# FINAL_COMMON_BOARD.net
KiCad netlist of a schematic drawn in EAGLE
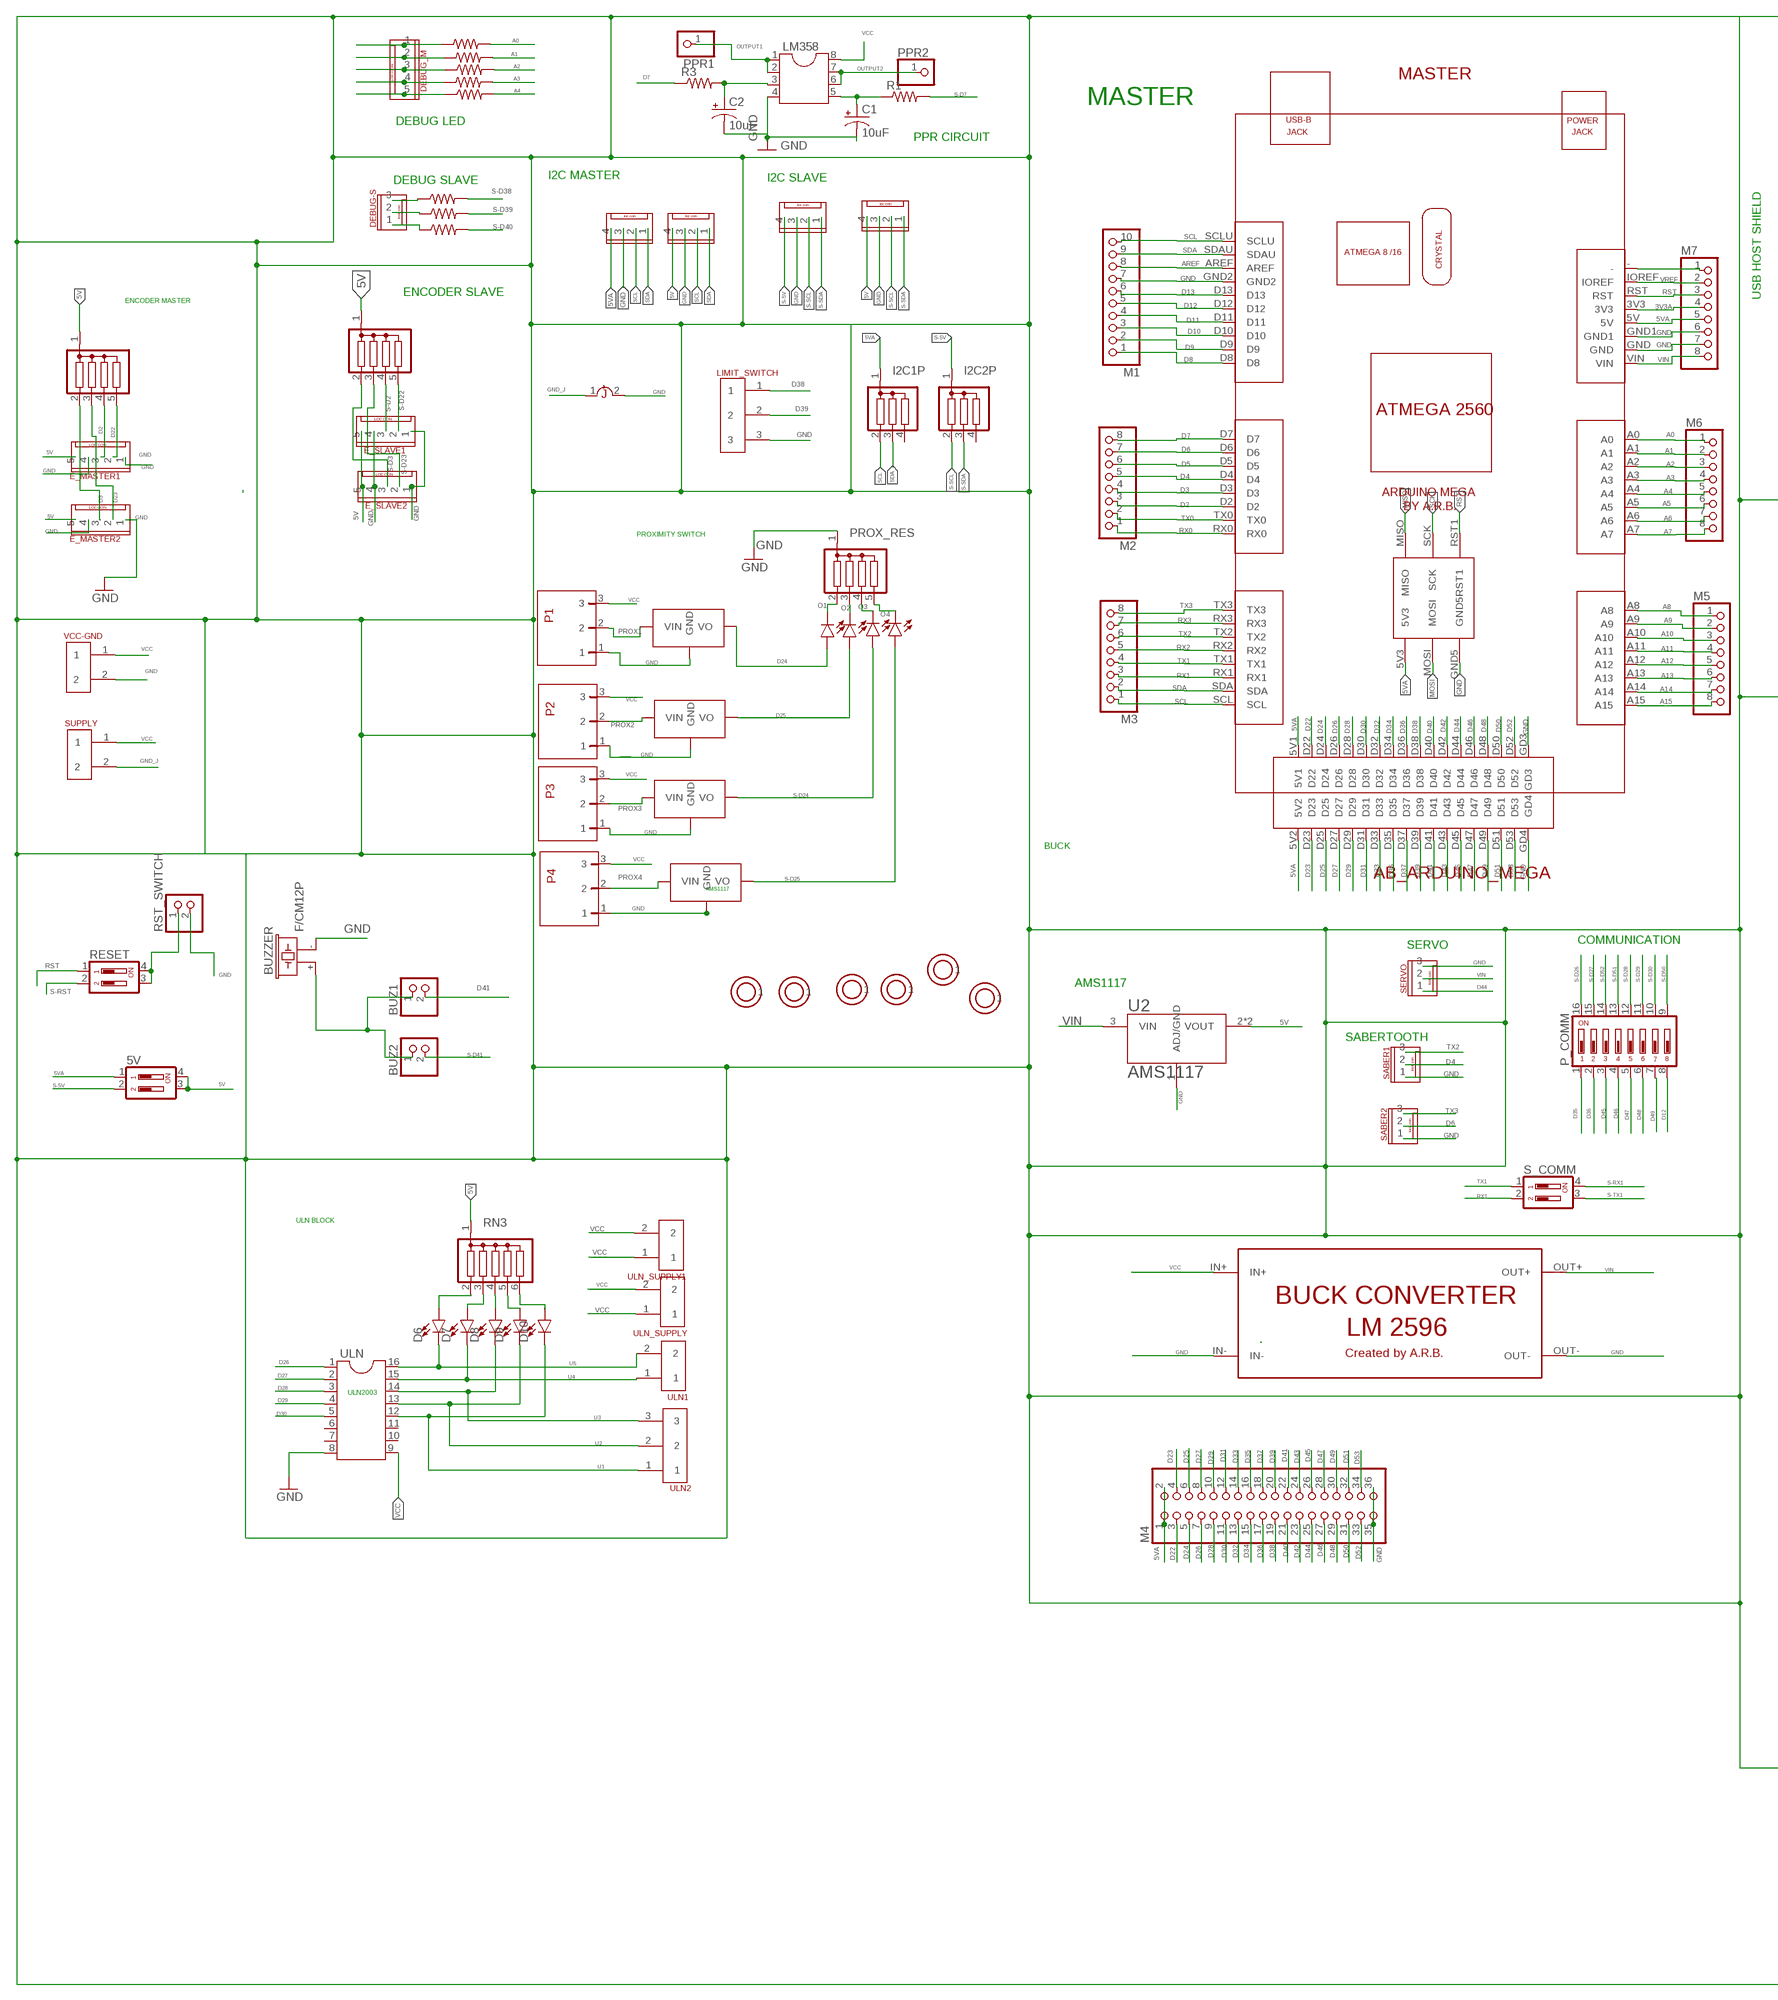
[diagram p0: schematic, sheet 1, part 1 of 2]
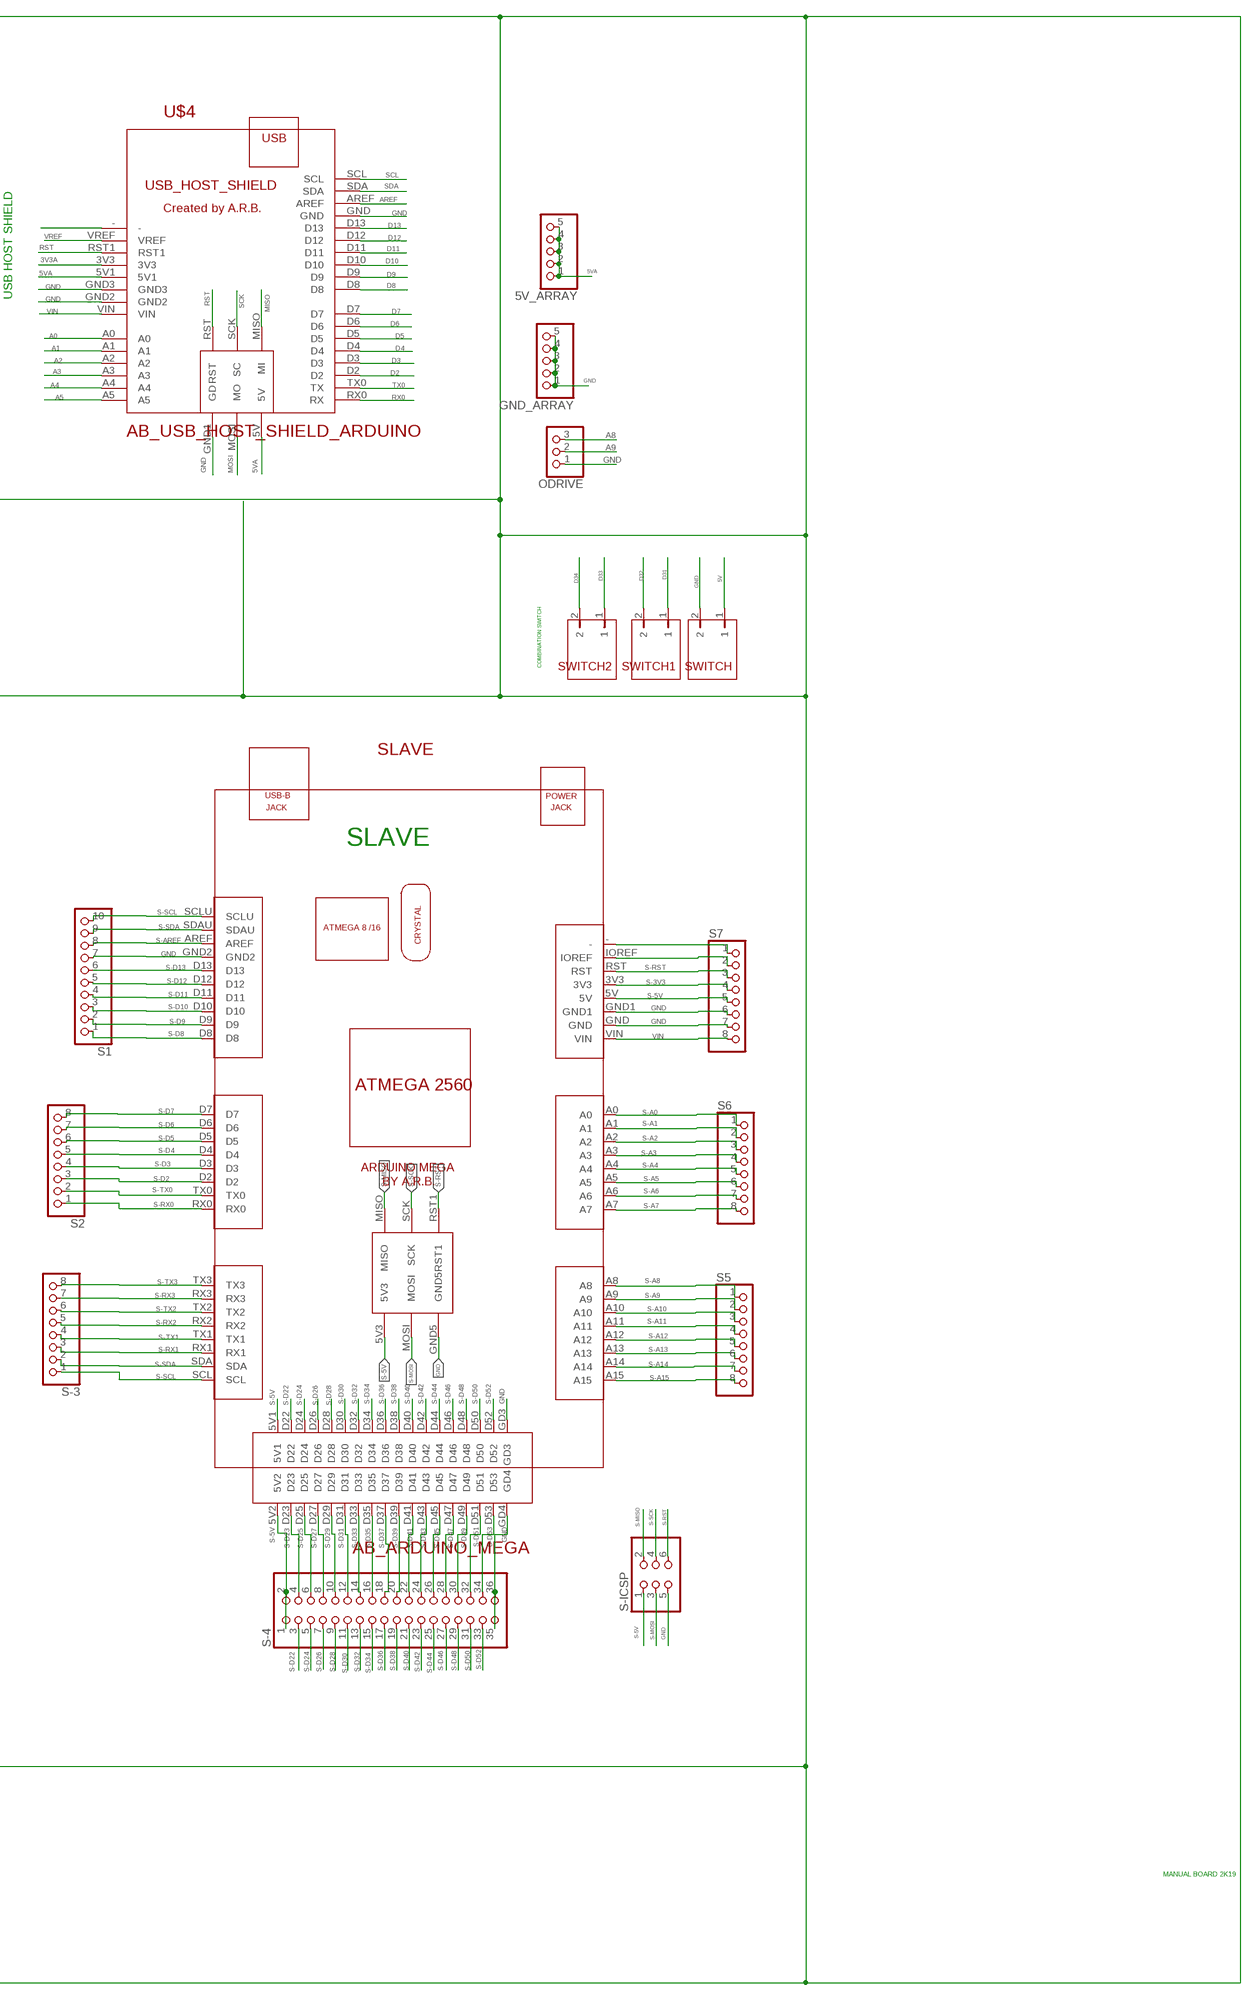
[diagram p1: schematic, sheet 1, part 2 of 2]

(export (version "E")
  (design (tool "Eeschema 10.0.6"))
  (components
    (comp (ref "5V")
      (value "DIP02YL")
      (footprint "eagle-import:DIP02YL")
      (libsource (lib "eagle-import") (part "DIP02YL"))
    )
    (comp (ref "5V_ARRAY")
      (value "PINHD-1X5")
      (footprint "eagle-import:1X05")
      (libsource (lib "eagle-import") (part "PINHD-1X5"))
    )
    (comp (ref "BUZ1")
      (value "PINHD-1X2")
      (footprint "eagle-import:1X02")
      (libsource (lib "eagle-import") (part "PINHD-1X2"))
    )
    (comp (ref "BUZ2")
      (value "PINHD-1X2")
      (footprint "eagle-import:1X02")
      (libsource (lib "eagle-import") (part "PINHD-1X2"))
    )
    (comp (ref "BUZZER")
      (value "F/CM12P")
      (footprint "eagle-import:F_CM12P")
      (libsource (lib "eagle-import") (part "F/CM12P"))
    )
    (comp (ref "C1")
      (value "10uF")
      (footprint "eagle-import:CPOL-RADIAL-2.5MM-5MM")
      (libsource (lib "eagle-import") (part "10UF-POLAR-RADIAL-2.5MM-25V-20%"))
    )
    (comp (ref "C2")
      (value "10uF")
      (footprint "eagle-import:CPOL-RADIAL-2.5MM-5MM")
      (libsource (lib "eagle-import") (part "10UF-POLAR-RADIAL-2.5MM-25V-20%"))
    )
    (comp (ref "D1")
      (value "LED-3MM-NO_SILK")
      (footprint "eagle-import:LED_3MM-NS")
      (libsource (lib "eagle-import") (part "LED-3MM-NO_SILK"))
    )
    (comp (ref "D2")
      (value "LED-3MM-NO_SILK")
      (footprint "eagle-import:LED_3MM-NS")
      (libsource (lib "eagle-import") (part "LED-3MM-NO_SILK"))
    )
    (comp (ref "D3")
      (value "LED-3MM-NO_SILK")
      (footprint "eagle-import:LED_3MM-NS")
      (libsource (lib "eagle-import") (part "LED-3MM-NO_SILK"))
    )
    (comp (ref "D6")
      (value "LED-3MM-NO_SILK")
      (footprint "eagle-import:LED_3MM-NS")
      (libsource (lib "eagle-import") (part "LED-3MM-NO_SILK"))
    )
    (comp (ref "D7")
      (value "LED-3MM-NO_SILK")
      (footprint "eagle-import:LED_3MM-NS")
      (libsource (lib "eagle-import") (part "LED-3MM-NO_SILK"))
    )
    (comp (ref "D8")
      (value "LED-3MM-NO_SILK")
      (footprint "eagle-import:LED_3MM-NS")
      (libsource (lib "eagle-import") (part "LED-3MM-NO_SILK"))
    )
    (comp (ref "D9")
      (value "LED-3MM-NO_SILK")
      (footprint "eagle-import:LED_3MM-NS")
      (libsource (lib "eagle-import") (part "LED-3MM-NO_SILK"))
    )
    (comp (ref "D10")
      (value "LED-3MM-NO_SILK")
      (footprint "eagle-import:LED_3MM-NS")
      (libsource (lib "eagle-import") (part "LED-3MM-NO_SILK"))
    )
    (comp (ref "D14")
      (value "LED-3MM-NO_SILK")
      (footprint "eagle-import:LED_3MM-NS")
      (libsource (lib "eagle-import") (part "LED-3MM-NO_SILK"))
    )
    (comp (ref "DEBUG-S")
      (value "AB_3PIN_LOC_CONNECTOR")
      (footprint "eagle-import:AB_3PIN_LOC_CONNECTOR")
      (libsource (lib "eagle-import") (part "AB_3PIN_LOC_CONNECTOR"))
    )
    (comp (ref "DEBUG_M")
      (value "AB_5PIN_LOC_CONNECTOR")
      (footprint "eagle-import:AB_5PIN_LOC_CONNECTOR")
      (libsource (lib "eagle-import") (part "AB_5PIN_LOC_CONNECTOR"))
    )
    (comp (ref "E_MASTER1")
      (value "AB_5PIN_LOC_CONNECTOR")
      (footprint "eagle-import:AB_5PIN_LOC_CONNECTOR")
      (libsource (lib "eagle-import") (part "AB_5PIN_LOC_CONNECTOR"))
    )
    (comp (ref "E_MASTER2")
      (value "AB_5PIN_LOC_CONNECTOR")
      (footprint "eagle-import:AB_5PIN_LOC_CONNECTOR")
      (libsource (lib "eagle-import") (part "AB_5PIN_LOC_CONNECTOR"))
    )
    (comp (ref "E_SLAVE1")
      (value "AB_5PIN_LOC_CONNECTOR")
      (footprint "eagle-import:AB_5PIN_LOC_CONNECTOR")
      (libsource (lib "eagle-import") (part "AB_5PIN_LOC_CONNECTOR"))
    )
    (comp (ref "E_SLAVE2")
      (value "AB_5PIN_LOC_CONNECTOR")
      (footprint "eagle-import:AB_5PIN_LOC_CONNECTOR")
      (libsource (lib "eagle-import") (part "AB_5PIN_LOC_CONNECTOR"))
    )
    (comp (ref "GND_ARRAY")
      (value "PINHD-1X5")
      (footprint "eagle-import:1X05")
      (libsource (lib "eagle-import") (part "PINHD-1X5"))
    )
    (comp (ref "I2C1P")
      (value "G03R")
      (footprint "eagle-import:SIL4")
      (libsource (lib "eagle-import") (part "G03R"))
    )
    (comp (ref "I2C2P")
      (value "G03R")
      (footprint "eagle-import:SIL4")
      (libsource (lib "eagle-import") (part "G03R"))
    )
    (comp (ref "IMU_BLOCK2")
      (value "AB_4PIN_LOC_CONNECTOR")
      (footprint "eagle-import:AB_4PIN_LOC_CONNECTOR")
      (libsource (lib "eagle-import") (part "AB_4PIN_LOC_CONNECTOR"))
    )
    (comp (ref "IMU_BLOCK3")
      (value "AB_4PIN_LOC_CONNECTOR")
      (footprint "eagle-import:AB_4PIN_LOC_CONNECTOR")
      (libsource (lib "eagle-import") (part "AB_4PIN_LOC_CONNECTOR"))
    )
    (comp (ref "IMU_BLOCK4")
      (value "AB_4PIN_LOC_CONNECTOR")
      (footprint "eagle-import:AB_4PIN_LOC_CONNECTOR")
      (libsource (lib "eagle-import") (part "AB_4PIN_LOC_CONNECTOR"))
    )
    (comp (ref "IMU_MASTER")
      (value "AB_4PIN_LOC_CONNECTOR")
      (footprint "eagle-import:AB_4PIN_LOC_CONNECTOR")
      (libsource (lib "eagle-import") (part "AB_4PIN_LOC_CONNECTOR"))
    )
    (comp (ref "LIMIT_SWITCH")
      (value "AB_SCREW_TER_5MM_3PIN")
      (footprint "eagle-import:AB_SCREW_TER_5MM_3PIN")
      (libsource (lib "eagle-import") (part "AB_SCREW_TER_5MM_3PIN"))
    )
    (comp (ref "LM358")
      (value "DIL8")
      (footprint "eagle-import:DIL08")
      (libsource (lib "eagle-import") (part "DIL8"))
    )
    (comp (ref "M1")
      (value "PINHD-1X10")
      (footprint "eagle-import:1X10")
      (libsource (lib "eagle-import") (part "PINHD-1X10"))
    )
    (comp (ref "M2")
      (value "PINHD-1X8")
      (footprint "eagle-import:1X08")
      (libsource (lib "eagle-import") (part "PINHD-1X8"))
    )
    (comp (ref "M3")
      (value "PINHD-1X8")
      (footprint "eagle-import:1X08")
      (libsource (lib "eagle-import") (part "PINHD-1X8"))
    )
    (comp (ref "M4")
      (value "PINHD-2X18")
      (footprint "eagle-import:2X18")
      (libsource (lib "eagle-import") (part "PINHD-2X18"))
    )
    (comp (ref "M5")
      (value "PINHD-1X8")
      (footprint "eagle-import:1X08")
      (libsource (lib "eagle-import") (part "PINHD-1X8"))
    )
    (comp (ref "M6")
      (value "PINHD-1X8")
      (footprint "eagle-import:1X08")
      (libsource (lib "eagle-import") (part "PINHD-1X8"))
    )
    (comp (ref "M7")
      (value "PINHD-1X8")
      (footprint "eagle-import:1X08")
      (libsource (lib "eagle-import") (part "PINHD-1X8"))
    )
    (comp (ref "MASTER")
      (value "AB_ARDUINO_MEGA")
      (footprint "eagle-import:AB_ARDUINO_MEGA")
      (libsource (lib "eagle-import") (part "AB_ARDUINO_MEGA"))
    )
    (comp (ref "ODRIVE")
      (value "PINHD-1X3")
      (footprint "eagle-import:1X03")
      (libsource (lib "eagle-import") (part "PINHD-1X3"))
    )
    (comp (ref "P1")
      (value "P1")
      (footprint "eagle-import:AB_RIGHT_TER_BLK_3PIN")
      (libsource (lib "eagle-import") (part "AB_RIGHT_TER_BLK_3PIN"))
    )
    (comp (ref "P2")
      (value "P2")
      (footprint "eagle-import:AB_RIGHT_TER_BLK_3PIN")
      (libsource (lib "eagle-import") (part "AB_RIGHT_TER_BLK_3PIN"))
    )
    (comp (ref "P3")
      (value "P3")
      (footprint "eagle-import:AB_RIGHT_TER_BLK_3PIN")
      (libsource (lib "eagle-import") (part "AB_RIGHT_TER_BLK_3PIN"))
    )
    (comp (ref "P4")
      (value "P4")
      (footprint "eagle-import:AB_RIGHT_TER_BLK_3PIN")
      (libsource (lib "eagle-import") (part "AB_RIGHT_TER_BLK_3PIN"))
    )
    (comp (ref "PPR1")
      (value "PINHD-1X1")
      (footprint "eagle-import:1X01")
      (libsource (lib "eagle-import") (part "PINHD-1X1"))
    )
    (comp (ref "PPR2")
      (value "PINHD-1X1")
      (footprint "eagle-import:1X01")
      (libsource (lib "eagle-import") (part "PINHD-1X1"))
    )
    (comp (ref "PROX_RES")
      (value "G04R")
      (footprint "eagle-import:SIL5")
      (libsource (lib "eagle-import") (part "G04R"))
    )
    (comp (ref "PULL_MASTER")
      (value "G04R")
      (footprint "eagle-import:SIL5")
      (libsource (lib "eagle-import") (part "G04R"))
    )
    (comp (ref "PULL_SLAVE")
      (value "G04R")
      (footprint "eagle-import:SIL5")
      (libsource (lib "eagle-import") (part "G04R"))
    )
    (comp (ref "P_COMM")
      (value "DIP08YL")
      (footprint "eagle-import:DIP08YL")
      (libsource (lib "eagle-import") (part "DIP08YL"))
    )
    (comp (ref "R1")
      (value "R-US_0204/7")
      (footprint "eagle-import:0204_7")
      (libsource (lib "eagle-import") (part "R-US_0204/7"))
    )
    (comp (ref "R2")
      (value "R-US_0204/7")
      (footprint "eagle-import:0204_7")
      (libsource (lib "eagle-import") (part "R-US_0204/7"))
    )
    (comp (ref "R3")
      (value "R-US_0204/7")
      (footprint "eagle-import:0204_7")
      (libsource (lib "eagle-import") (part "R-US_0204/7"))
    )
    (comp (ref "R4")
      (value "R-US_0204/7")
      (footprint "eagle-import:0204_7")
      (libsource (lib "eagle-import") (part "R-US_0204/7"))
    )
    (comp (ref "R5")
      (value "R-US_0204/7")
      (footprint "eagle-import:0204_7")
      (libsource (lib "eagle-import") (part "R-US_0204/7"))
    )
    (comp (ref "R6")
      (value "R-US_0204/7")
      (footprint "eagle-import:0204_7")
      (libsource (lib "eagle-import") (part "R-US_0204/7"))
    )
    (comp (ref "R7")
      (value "R-US_0204/7")
      (footprint "eagle-import:0204_7")
      (libsource (lib "eagle-import") (part "R-US_0204/7"))
    )
    (comp (ref "R8")
      (value "R-US_0204/7")
      (footprint "eagle-import:0204_7")
      (libsource (lib "eagle-import") (part "R-US_0204/7"))
    )
    (comp (ref "R9")
      (value "R-US_0204/7")
      (footprint "eagle-import:0204_7")
      (libsource (lib "eagle-import") (part "R-US_0204/7"))
    )
    (comp (ref "R10")
      (value "R-US_0204/7")
      (footprint "eagle-import:0204_7")
      (libsource (lib "eagle-import") (part "R-US_0204/7"))
    )
    (comp (ref "RESET")
      (value "DIP02YL")
      (footprint "eagle-import:DIP02YL")
      (libsource (lib "eagle-import") (part "DIP02YL"))
    )
    (comp (ref "RN3")
      (value "G05R")
      (footprint "eagle-import:SIL6")
      (libsource (lib "eagle-import") (part "G05R"))
    )
    (comp (ref "RST_SWITCH")
      (value "PINHD-1X2")
      (footprint "eagle-import:1X02")
      (libsource (lib "eagle-import") (part "PINHD-1X2"))
    )
    (comp (ref "S-3")
      (value "PINHD-1X8")
      (footprint "eagle-import:1X08")
      (libsource (lib "eagle-import") (part "PINHD-1X8"))
    )
    (comp (ref "S-4")
      (value "PINHD-2X18")
      (footprint "eagle-import:2X18")
      (libsource (lib "eagle-import") (part "PINHD-2X18"))
    )
    (comp (ref "S-ICSP")
      (value "PINHD-2X3")
      (footprint "eagle-import:2X03")
      (libsource (lib "eagle-import") (part "PINHD-2X3"))
    )
    (comp (ref "S1")
      (value "PINHD-1X10")
      (footprint "eagle-import:1X10")
      (libsource (lib "eagle-import") (part "PINHD-1X10"))
    )
    (comp (ref "S2")
      (value "PINHD-1X8")
      (footprint "eagle-import:1X08")
      (libsource (lib "eagle-import") (part "PINHD-1X8"))
    )
    (comp (ref "S5")
      (value "PINHD-1X8")
      (footprint "eagle-import:1X08")
      (libsource (lib "eagle-import") (part "PINHD-1X8"))
    )
    (comp (ref "S6")
      (value "PINHD-1X8")
      (footprint "eagle-import:1X08")
      (libsource (lib "eagle-import") (part "PINHD-1X8"))
    )
    (comp (ref "S7")
      (value "PINHD-1X8")
      (footprint "eagle-import:1X08")
      (libsource (lib "eagle-import") (part "PINHD-1X8"))
    )
    (comp (ref "SABER1")
      (value "AB_3PIN_LOC_CONNECTOR")
      (footprint "eagle-import:AB_3PIN_LOC_CONNECTOR")
      (libsource (lib "eagle-import") (part "AB_3PIN_LOC_CONNECTOR"))
    )
    (comp (ref "SABER2")
      (value "AB_3PIN_LOC_CONNECTOR")
      (footprint "eagle-import:AB_3PIN_LOC_CONNECTOR")
      (libsource (lib "eagle-import") (part "AB_3PIN_LOC_CONNECTOR"))
    )
    (comp (ref "SERVO")
      (value "AB_3PIN_LOC_CONNECTOR")
      (footprint "eagle-import:AB_3PIN_LOC_CONNECTOR")
      (libsource (lib "eagle-import") (part "AB_3PIN_LOC_CONNECTOR"))
    )
    (comp (ref "SLAVE")
      (value "AB_ARDUINO_MEGA")
      (footprint "eagle-import:AB_ARDUINO_MEGA")
      (libsource (lib "eagle-import") (part "AB_ARDUINO_MEGA"))
    )
    (comp (ref "SUPPLY")
      (value "AB_SCREW_TERMINAL_5MM_2PIN")
      (footprint "eagle-import:AB_SCREW_TERMINAL_5MM_2PIN")
      (libsource (lib "eagle-import") (part "AB_SCREW_TERMINAL_5MM_2PIN"))
    )
    (comp (ref "SWITCH")
      (value "AB_RIGHT_TER_BLK")
      (footprint "eagle-import:AB_RIGHT_TER_BLK")
      (libsource (lib "eagle-import") (part "AB_RIGHT_TER_BLK"))
    )
    (comp (ref "SWITCH1")
      (value "AB_RIGHT_TER_BLK")
      (footprint "eagle-import:AB_RIGHT_TER_BLK")
      (libsource (lib "eagle-import") (part "AB_RIGHT_TER_BLK"))
    )
    (comp (ref "SWITCH2")
      (value "AB_RIGHT_TER_BLK")
      (footprint "eagle-import:AB_RIGHT_TER_BLK")
      (libsource (lib "eagle-import") (part "AB_RIGHT_TER_BLK"))
    )
    (comp (ref "S_COMM")
      (value "DIP02YL")
      (footprint "eagle-import:DIP02YL")
      (libsource (lib "eagle-import") (part "DIP02YL"))
    )
    (comp (ref "U$1")
      (value "PLATED_DRILL_3.5MM")
      (footprint "eagle-import:PLATED_DRILL_3.5MM")
      (libsource (lib "eagle-import") (part "PLATED_DRILL_3.5MM"))
    )
    (comp (ref "U$2")
      (value "PLATED_DRILL_3.5MM")
      (footprint "eagle-import:PLATED_DRILL_3.5MM")
      (libsource (lib "eagle-import") (part "PLATED_DRILL_3.5MM"))
    )
    (comp (ref "U$3")
      (value "AB_LM2596_BUCK_CONVERTER")
      (footprint "eagle-import:AB_LM2596_BUCK_CONVERTER")
      (libsource (lib "eagle-import") (part "AB_LM2596_BUCK_CONVERTER"))
    )
    (comp (ref "U$4")
      (value "AB_USB_HOST_SHIELD_ARDUINO")
      (footprint "eagle-import:AB_USB_HOST_SHIELD_ARDUINO")
      (libsource (lib "eagle-import") (part "AB_USB_HOST_SHIELD_ARDUINO"))
    )
    (comp (ref "U$5")
      (value "PLATED_DRILL_3.5MM")
      (footprint "eagle-import:PLATED_DRILL_3.5MM")
      (libsource (lib "eagle-import") (part "PLATED_DRILL_3.5MM"))
    )
    (comp (ref "U$6")
      (value "PLATED_DRILL_3.5MM")
      (footprint "eagle-import:PLATED_DRILL_3.5MM")
      (libsource (lib "eagle-import") (part "PLATED_DRILL_3.5MM"))
    )
    (comp (ref "U$7")
      (value "PLATED_DRILL_3.5MM")
      (footprint "eagle-import:PLATED_DRILL_3.5MM")
      (libsource (lib "eagle-import") (part "PLATED_DRILL_3.5MM"))
    )
    (comp (ref "U$8")
      (value "PLATED_DRILL_3.5MM")
      (footprint "eagle-import:PLATED_DRILL_3.5MM")
      (libsource (lib "eagle-import") (part "PLATED_DRILL_3.5MM"))
    )
    (comp (ref "U$23")
      (value "AB_7805_FLAT")
      (footprint "eagle-import:AB_7805_FLAT")
      (libsource (lib "eagle-import") (part "AB_7805_FLAT"))
    )
    (comp (ref "U$24")
      (value "AB_7805_FLAT")
      (footprint "eagle-import:AB_7805_FLAT")
      (libsource (lib "eagle-import") (part "AB_7805_FLAT"))
    )
    (comp (ref "U$25")
      (value "AB_7805_FLAT")
      (footprint "eagle-import:AB_7805_FLAT")
      (libsource (lib "eagle-import") (part "AB_7805_FLAT"))
    )
    (comp (ref "U$26")
      (value "AB_7805_FLAT")
      (footprint "eagle-import:AB_7805_FLAT")
      (libsource (lib "eagle-import") (part "AB_7805_FLAT"))
    )
    (comp (ref "U$35")
      (value "AB_JUMPER_ONE_WAY")
      (footprint "eagle-import:AB_JUMPER_ONE_WAY")
      (libsource (lib "eagle-import") (part "AB_JUMPER_ONE_WAY"))
    )
    (comp (ref "U2")
      (value "AMS1117")
      (footprint "eagle-import:SOT229P700X180-4N")
      (fields (field (name "MF") "Seeed Technology"))
      (libsource (lib "eagle-import") (part "AMS1117"))
    )
    (comp (ref "ULN")
      (value "DIL16")
      (footprint "eagle-import:DIL16")
      (libsource (lib "eagle-import") (part "DIL16"))
    )
    (comp (ref "ULN1")
      (value "AB_SCREW_TERMINAL_5MM_2PIN")
      (footprint "eagle-import:AB_SCREW_TERMINAL_5MM_2PIN")
      (libsource (lib "eagle-import") (part "AB_SCREW_TERMINAL_5MM_2PIN"))
    )
    (comp (ref "ULN2")
      (value "AB_SCREW_TER_5MM_3PIN")
      (footprint "eagle-import:AB_SCREW_TER_5MM_3PIN")
      (libsource (lib "eagle-import") (part "AB_SCREW_TER_5MM_3PIN"))
    )
    (comp (ref "ULN_SUPPLY")
      (value "AB_SCREW_TERMINAL_5MM_2PIN")
      (footprint "eagle-import:AB_SCREW_TERMINAL_5MM_2PIN")
      (libsource (lib "eagle-import") (part "AB_SCREW_TERMINAL_5MM_2PIN"))
    )
    (comp (ref "ULN_SUPPLY1")
      (value "AB_SCREW_TERMINAL_5MM_2PIN")
      (footprint "eagle-import:AB_SCREW_TERMINAL_5MM_2PIN")
      (libsource (lib "eagle-import") (part "AB_SCREW_TERMINAL_5MM_2PIN"))
    )
    (comp (ref "VCC-GND")
      (value "AB_SCREW_TERMINAL_5MM_2PIN")
      (footprint "eagle-import:AB_SCREW_TERMINAL_5MM_2PIN")
      (libsource (lib "eagle-import") (part "AB_SCREW_TERMINAL_5MM_2PIN"))
    )
  )
  (nets
    (net (code "1") (name "/3V3A") (class "Default")
      (node (ref "M7") (pin "4") (pinfunction "4_4") (pintype "passive"))
      (node (ref "MASTER") (pin "3V3") (pinfunction "3V3_3V3") (pintype "bidirectional"))
      (node (ref "U$4") (pin "3V3") (pinfunction "3V3_3V3") (pintype "bidirectional"))
    )
    (net (code "2") (name "/A0") (class "Default")
      (node (ref "M6") (pin "1") (pinfunction "1_1") (pintype "passive"))
      (node (ref "MASTER") (pin "A0") (pinfunction "A0_A0") (pintype "bidirectional"))
      (node (ref "R2") (pin "2") (pinfunction "2_2") (pintype "passive"))
      (node (ref "U$4") (pin "A0") (pinfunction "A0_A0") (pintype "bidirectional"))
    )
    (net (code "3") (name "/A1") (class "Default")
      (node (ref "M6") (pin "2") (pinfunction "2_2") (pintype "passive"))
      (node (ref "MASTER") (pin "A1") (pinfunction "A1_A1") (pintype "bidirectional"))
      (node (ref "R4") (pin "2") (pinfunction "2_2") (pintype "passive"))
      (node (ref "U$4") (pin "A1") (pinfunction "A1_A1") (pintype "bidirectional"))
    )
    (net (code "4") (name "/A2") (class "Default")
      (node (ref "M6") (pin "3") (pinfunction "3_3") (pintype "passive"))
      (node (ref "MASTER") (pin "A2") (pinfunction "A2_A2") (pintype "bidirectional"))
      (node (ref "R5") (pin "2") (pinfunction "2_2") (pintype "passive"))
      (node (ref "U$4") (pin "A2") (pinfunction "A2_A2") (pintype "bidirectional"))
    )
    (net (code "5") (name "/A3") (class "Default")
      (node (ref "M6") (pin "4") (pinfunction "4_4") (pintype "passive"))
      (node (ref "MASTER") (pin "A3") (pinfunction "A3_A3") (pintype "bidirectional"))
      (node (ref "R6") (pin "2") (pinfunction "2_2") (pintype "passive"))
      (node (ref "U$4") (pin "A3") (pinfunction "A3_A3") (pintype "bidirectional"))
    )
    (net (code "6") (name "/A4") (class "Default")
      (node (ref "M6") (pin "5") (pinfunction "5_5") (pintype "passive"))
      (node (ref "MASTER") (pin "A4") (pinfunction "A4_A4") (pintype "bidirectional"))
      (node (ref "R7") (pin "2") (pinfunction "2_2") (pintype "passive"))
      (node (ref "U$4") (pin "A4") (pinfunction "A4_A4") (pintype "bidirectional"))
    )
    (net (code "7") (name "/A5") (class "Default")
      (node (ref "M6") (pin "6") (pinfunction "6_6") (pintype "passive"))
      (node (ref "MASTER") (pin "A5") (pinfunction "A5_A5") (pintype "bidirectional"))
      (node (ref "U$4") (pin "A5") (pinfunction "A5_A5") (pintype "bidirectional"))
    )
    (net (code "8") (name "/A6") (class "Default")
      (node (ref "M6") (pin "7") (pinfunction "7_7") (pintype "passive"))
      (node (ref "MASTER") (pin "A6") (pinfunction "A6_A6") (pintype "bidirectional"))
    )
    (net (code "9") (name "/A7") (class "Default")
      (node (ref "M6") (pin "8") (pinfunction "8_8") (pintype "passive"))
      (node (ref "MASTER") (pin "A7") (pinfunction "A7_A7") (pintype "bidirectional"))
    )
    (net (code "10") (name "/A8") (class "Default")
      (node (ref "M5") (pin "1") (pinfunction "1_1") (pintype "passive"))
      (node (ref "MASTER") (pin "A8") (pinfunction "A8_A8") (pintype "bidirectional"))
      (node (ref "ODRIVE") (pin "3") (pinfunction "3_3") (pintype "passive"))
    )
    (net (code "11") (name "/A9") (class "Default")
      (node (ref "M5") (pin "2") (pinfunction "2_2") (pintype "passive"))
      (node (ref "MASTER") (pin "A9") (pinfunction "A9_A9") (pintype "bidirectional"))
      (node (ref "ODRIVE") (pin "2") (pinfunction "2_2") (pintype "passive"))
    )
    (net (code "12") (name "/A10") (class "Default")
      (node (ref "M5") (pin "3") (pinfunction "3_3") (pintype "passive"))
      (node (ref "MASTER") (pin "A10") (pinfunction "A10_A10") (pintype "bidirectional"))
    )
    (net (code "13") (name "/A11") (class "Default")
      (node (ref "M5") (pin "4") (pinfunction "4_4") (pintype "passive"))
      (node (ref "MASTER") (pin "A11") (pinfunction "A11_A11") (pintype "bidirectional"))
    )
    (net (code "14") (name "/A12") (class "Default")
      (node (ref "M5") (pin "5") (pinfunction "5_5") (pintype "passive"))
      (node (ref "MASTER") (pin "A12") (pinfunction "A12_A12") (pintype "bidirectional"))
    )
    (net (code "15") (name "/A13") (class "Default")
      (node (ref "M5") (pin "6") (pinfunction "6_6") (pintype "passive"))
      (node (ref "MASTER") (pin "A13") (pinfunction "A13_A13") (pintype "bidirectional"))
    )
    (net (code "16") (name "/A14") (class "Default")
      (node (ref "M5") (pin "7") (pinfunction "7_7") (pintype "passive"))
      (node (ref "MASTER") (pin "A14") (pinfunction "A14_A14") (pintype "bidirectional"))
    )
    (net (code "17") (name "/A15") (class "Default")
      (node (ref "M5") (pin "8") (pinfunction "8_8") (pintype "passive"))
      (node (ref "MASTER") (pin "A15") (pinfunction "A15_A15") (pintype "bidirectional"))
    )
    (net (code "18") (name "/AREF") (class "Default")
      (node (ref "M1") (pin "8") (pinfunction "8_8") (pintype "passive"))
      (node (ref "MASTER") (pin "AREF") (pinfunction "AREF_AREF") (pintype "bidirectional"))
      (node (ref "U$4") (pin "AREF") (pinfunction "AREF_AREF") (pintype "bidirectional"))
    )
    (net (code "19") (name "/D2") (class "Default")
      (node (ref "E_MASTER1") (pin "3") (pinfunction "3_3") (pintype "bidirectional"))
      (node (ref "M2") (pin "3") (pinfunction "3_3") (pintype "passive"))
      (node (ref "MASTER") (pin "D2") (pinfunction "D2_D2") (pintype "bidirectional"))
      (node (ref "PULL_MASTER") (pin "4") (pinfunction "4_4") (pintype "passive"))
      (node (ref "U$4") (pin "D2") (pinfunction "D2_D2") (pintype "bidirectional"))
    )
    (net (code "20") (name "/D3") (class "Default")
      (node (ref "E_MASTER2") (pin "3") (pinfunction "3_3") (pintype "bidirectional"))
      (node (ref "M2") (pin "4") (pinfunction "4_4") (pintype "passive"))
      (node (ref "MASTER") (pin "D3") (pinfunction "D3_D3") (pintype "bidirectional"))
      (node (ref "PULL_MASTER") (pin "2") (pinfunction "2_2") (pintype "passive"))
      (node (ref "U$4") (pin "D3") (pinfunction "D3_D3") (pintype "bidirectional"))
    )
    (net (code "21") (name "/D4") (class "Default")
      (node (ref "M2") (pin "5") (pinfunction "5_5") (pintype "passive"))
      (node (ref "MASTER") (pin "D4") (pinfunction "D4_D4") (pintype "bidirectional"))
      (node (ref "SABER1") (pin "2") (pinfunction "2_2") (pintype "bidirectional"))
      (node (ref "U$4") (pin "D4") (pinfunction "D4_D4") (pintype "bidirectional"))
    )
    (net (code "22") (name "/D5") (class "Default")
      (node (ref "M2") (pin "6") (pinfunction "6_6") (pintype "passive"))
      (node (ref "MASTER") (pin "D5") (pinfunction "D5_D5") (pintype "bidirectional"))
      (node (ref "U$4") (pin "D5") (pinfunction "D5_D5") (pintype "bidirectional"))
    )
    (net (code "23") (name "/D6") (class "Default")
      (node (ref "M2") (pin "7") (pinfunction "7_7") (pintype "passive"))
      (node (ref "MASTER") (pin "D6") (pinfunction "D6_D6") (pintype "bidirectional"))
      (node (ref "SABER2") (pin "2") (pinfunction "2_2") (pintype "bidirectional"))
      (node (ref "U$4") (pin "D6") (pinfunction "D6_D6") (pintype "bidirectional"))
    )
    (net (code "24") (name "/D7") (class "Default")
      (node (ref "M2") (pin "8") (pinfunction "8_8") (pintype "passive"))
      (node (ref "MASTER") (pin "D7") (pinfunction "D7_D7") (pintype "bidirectional"))
      (node (ref "R3") (pin "1") (pinfunction "1_1") (pintype "passive"))
      (node (ref "U$4") (pin "D7") (pinfunction "D7_D7") (pintype "bidirectional"))
    )
    (net (code "25") (name "/D8") (class "Default")
      (node (ref "M1") (pin "1") (pinfunction "1_1") (pintype "passive"))
      (node (ref "MASTER") (pin "D8") (pinfunction "D8_D8") (pintype "bidirectional"))
      (node (ref "U$4") (pin "D8") (pinfunction "D8_D8") (pintype "bidirectional"))
    )
    (net (code "26") (name "/D9") (class "Default")
      (node (ref "M1") (pin "2") (pinfunction "2_2") (pintype "passive"))
      (node (ref "MASTER") (pin "D9") (pinfunction "D9_D9") (pintype "bidirectional"))
      (node (ref "U$4") (pin "D9") (pinfunction "D9_D9") (pintype "bidirectional"))
    )
    (net (code "27") (name "/D10") (class "Default")
      (node (ref "M1") (pin "3") (pinfunction "3_3") (pintype "passive"))
      (node (ref "MASTER") (pin "D10") (pinfunction "D10_D10") (pintype "bidirectional"))
      (node (ref "U$4") (pin "D10") (pinfunction "D10_D10") (pintype "bidirectional"))
    )
    (net (code "28") (name "/D11") (class "Default")
      (node (ref "M1") (pin "4") (pinfunction "4_4") (pintype "passive"))
      (node (ref "MASTER") (pin "D11") (pinfunction "D11_D11") (pintype "bidirectional"))
      (node (ref "U$4") (pin "D11") (pinfunction "D11_D11") (pintype "bidirectional"))
    )
    (net (code "29") (name "/D12") (class "Default")
      (node (ref "M1") (pin "5") (pinfunction "5_5") (pintype "passive"))
      (node (ref "MASTER") (pin "D12") (pinfunction "D12_D12") (pintype "bidirectional"))
      (node (ref "P_COMM") (pin "8") (pinfunction "8_8") (pintype "passive"))
      (node (ref "U$4") (pin "D12") (pinfunction "D12_D12") (pintype "bidirectional"))
    )
    (net (code "30") (name "/D13") (class "Default")
      (node (ref "M1") (pin "6") (pinfunction "6_6") (pintype "passive"))
      (node (ref "MASTER") (pin "D13") (pinfunction "D13_D13") (pintype "bidirectional"))
      (node (ref "U$4") (pin "D13") (pinfunction "D13_D13") (pintype "bidirectional"))
    )
    (net (code "31") (name "/D22") (class "Default")
      (node (ref "E_MASTER1") (pin "2") (pinfunction "2_2") (pintype "bidirectional"))
      (node (ref "M4") (pin "3") (pinfunction "3_3") (pintype "passive"))
      (node (ref "MASTER") (pin "D22") (pinfunction "D22_D22") (pintype "bidirectional"))
      (node (ref "PULL_MASTER") (pin "5") (pinfunction "5_5") (pintype "passive"))
    )
    (net (code "32") (name "/D23") (class "Default")
      (node (ref "E_MASTER2") (pin "2") (pinfunction "2_2") (pintype "bidirectional"))
      (node (ref "M4") (pin "4") (pinfunction "4_4") (pintype "passive"))
      (node (ref "MASTER") (pin "D23") (pinfunction "D23_D23") (pintype "bidirectional"))
      (node (ref "PULL_MASTER") (pin "3") (pinfunction "3_3") (pintype "passive"))
    )
    (net (code "33") (name "/D24") (class "Default")
      (node (ref "D14") (pin "A") (pinfunction "A_A") (pintype "passive"))
      (node (ref "M4") (pin "5") (pinfunction "5_5") (pintype "passive"))
      (node (ref "MASTER") (pin "D24") (pinfunction "D24_D24") (pintype "bidirectional"))
      (node (ref "U$23") (pin "3") (pinfunction "VO_3") (pintype "bidirectional"))
    )
    (net (code "34") (name "/D25") (class "Default")
      (node (ref "D1") (pin "A") (pinfunction "A_A") (pintype "passive"))
      (node (ref "M4") (pin "6") (pinfunction "6_6") (pintype "passive"))
      (node (ref "MASTER") (pin "D25") (pinfunction "D25_D25") (pintype "bidirectional"))
      (node (ref "U$24") (pin "3") (pinfunction "VO_3") (pintype "bidirectional"))
    )
    (net (code "35") (name "/D26") (class "Default")
      (node (ref "M4") (pin "7") (pinfunction "7_7") (pintype "passive"))
      (node (ref "MASTER") (pin "D26") (pinfunction "D26_D26") (pintype "bidirectional"))
      (node (ref "ULN") (pin "1") (pinfunction "1_1") (pintype "passive"))
    )
    (net (code "36") (name "/D27") (class "Default")
      (node (ref "M4") (pin "8") (pinfunction "8_8") (pintype "passive"))
      (node (ref "MASTER") (pin "D27") (pinfunction "D27_D27") (pintype "bidirectional"))
      (node (ref "ULN") (pin "2") (pinfunction "2_2") (pintype "passive"))
    )
    (net (code "37") (name "/D28") (class "Default")
      (node (ref "M4") (pin "9") (pinfunction "9_9") (pintype "passive"))
      (node (ref "MASTER") (pin "D28") (pinfunction "D28_D28") (pintype "bidirectional"))
      (node (ref "ULN") (pin "3") (pinfunction "3_3") (pintype "passive"))
    )
    (net (code "38") (name "/D29") (class "Default")
      (node (ref "M4") (pin "10") (pinfunction "10_10") (pintype "passive"))
      (node (ref "MASTER") (pin "D29") (pinfunction "D29_D29") (pintype "bidirectional"))
      (node (ref "ULN") (pin "4") (pinfunction "4_4") (pintype "passive"))
    )
    (net (code "39") (name "/D30") (class "Default")
      (node (ref "M4") (pin "11") (pinfunction "11_11") (pintype "passive"))
      (node (ref "MASTER") (pin "D30") (pinfunction "D30_D30") (pintype "bidirectional"))
      (node (ref "ULN") (pin "5") (pinfunction "5_5") (pintype "passive"))
    )
    (net (code "40") (name "/D31") (class "Default")
      (node (ref "M4") (pin "12") (pinfunction "12_12") (pintype "passive"))
      (node (ref "MASTER") (pin "D31") (pinfunction "D31_D31") (pintype "bidirectional"))
      (node (ref "SWITCH1") (pin "1") (pinfunction "1_1") (pintype "bidirectional"))
    )
    (net (code "41") (name "/D32") (class "Default")
      (node (ref "M4") (pin "13") (pinfunction "13_13") (pintype "passive"))
      (node (ref "MASTER") (pin "D32") (pinfunction "D32_D32") (pintype "bidirectional"))
      (node (ref "SWITCH1") (pin "2") (pinfunction "2_2") (pintype "bidirectional"))
    )
    (net (code "42") (name "/D33") (class "Default")
      (node (ref "M4") (pin "14") (pinfunction "14_14") (pintype "passive"))
      (node (ref "MASTER") (pin "D33") (pinfunction "D33_D33") (pintype "bidirectional"))
      (node (ref "SWITCH2") (pin "1") (pinfunction "1_1") (pintype "bidirectional"))
    )
    (net (code "43") (name "/D34") (class "Default")
      (node (ref "M4") (pin "15") (pinfunction "15_15") (pintype "passive"))
      (node (ref "MASTER") (pin "D34") (pinfunction "D34_D34") (pintype "bidirectional"))
      (node (ref "SWITCH2") (pin "2") (pinfunction "2_2") (pintype "bidirectional"))
    )
    (net (code "44") (name "/D35") (class "Default")
      (node (ref "M4") (pin "16") (pinfunction "16_16") (pintype "passive"))
      (node (ref "MASTER") (pin "D35") (pinfunction "D35_D35") (pintype "bidirectional"))
      (node (ref "P_COMM") (pin "1") (pinfunction "1_1") (pintype "passive"))
    )
    (net (code "45") (name "/D36") (class "Default")
      (node (ref "M4") (pin "17") (pinfunction "17_17") (pintype "passive"))
      (node (ref "MASTER") (pin "D36") (pinfunction "D36_D36") (pintype "bidirectional"))
      (node (ref "P_COMM") (pin "2") (pinfunction "2_2") (pintype "passive"))
    )
    (net (code "46") (name "/D37") (class "Default")
      (node (ref "M4") (pin "18") (pinfunction "18_18") (pintype "passive"))
      (node (ref "MASTER") (pin "D37") (pinfunction "D37_D37") (pintype "bidirectional"))
    )
    (net (code "47") (name "/D38") (class "Default")
      (node (ref "LIMIT_SWITCH") (pin "1") (pinfunction "1_1") (pintype "bidirectional"))
      (node (ref "M4") (pin "19") (pinfunction "19_19") (pintype "passive"))
      (node (ref "MASTER") (pin "D38") (pinfunction "D38_D38") (pintype "bidirectional"))
    )
    (net (code "48") (name "/D39") (class "Default")
      (node (ref "LIMIT_SWITCH") (pin "2") (pinfunction "2_2") (pintype "bidirectional"))
      (node (ref "M4") (pin "20") (pinfunction "20_20") (pintype "passive"))
      (node (ref "MASTER") (pin "D39") (pinfunction "D39_D39") (pintype "bidirectional"))
    )
    (net (code "49") (name "/D40") (class "Default")
      (node (ref "M4") (pin "21") (pinfunction "21_21") (pintype "passive"))
      (node (ref "MASTER") (pin "D40") (pinfunction "D40_D40") (pintype "bidirectional"))
    )
    (net (code "50") (name "/D41") (class "Default")
      (node (ref "BUZ1") (pin "2") (pinfunction "2_2") (pintype "passive"))
      (node (ref "M4") (pin "22") (pinfunction "22_22") (pintype "passive"))
      (node (ref "MASTER") (pin "D41") (pinfunction "D41_D41") (pintype "bidirectional"))
    )
    (net (code "51") (name "/D42") (class "Default")
      (node (ref "M4") (pin "23") (pinfunction "23_23") (pintype "passive"))
      (node (ref "MASTER") (pin "D42") (pinfunction "D42_D42") (pintype "bidirectional"))
    )
    (net (code "52") (name "/D43") (class "Default")
      (node (ref "M4") (pin "24") (pinfunction "24_24") (pintype "passive"))
      (node (ref "MASTER") (pin "D43") (pinfunction "D43_D43") (pintype "bidirectional"))
    )
    (net (code "53") (name "/D44") (class "Default")
      (node (ref "M4") (pin "25") (pinfunction "25_25") (pintype "passive"))
      (node (ref "MASTER") (pin "D44") (pinfunction "D44_D44") (pintype "bidirectional"))
      (node (ref "SERVO") (pin "1") (pinfunction "1_1") (pintype "bidirectional"))
    )
    (net (code "54") (name "/D45") (class "Default")
      (node (ref "M4") (pin "26") (pinfunction "26_26") (pintype "passive"))
      (node (ref "MASTER") (pin "D45") (pinfunction "D45_D45") (pintype "bidirectional"))
      (node (ref "P_COMM") (pin "3") (pinfunction "3_3") (pintype "passive"))
    )
    (net (code "55") (name "/D46") (class "Default")
      (node (ref "M4") (pin "27") (pinfunction "27_27") (pintype "passive"))
      (node (ref "MASTER") (pin "D46") (pinfunction "D46_D46") (pintype "bidirectional"))
      (node (ref "P_COMM") (pin "4") (pinfunction "4_4") (pintype "passive"))
    )
    (net (code "56") (name "/D47") (class "Default")
      (node (ref "M4") (pin "28") (pinfunction "28_28") (pintype "passive"))
      (node (ref "MASTER") (pin "D47") (pinfunction "D47_D47") (pintype "bidirectional"))
      (node (ref "P_COMM") (pin "5") (pinfunction "5_5") (pintype "passive"))
    )
    (net (code "57") (name "/D48") (class "Default")
      (node (ref "M4") (pin "29") (pinfunction "29_29") (pintype "passive"))
      (node (ref "MASTER") (pin "D48") (pinfunction "D48_D48") (pintype "bidirectional"))
      (node (ref "P_COMM") (pin "6") (pinfunction "6_6") (pintype "passive"))
    )
    (net (code "58") (name "/D49") (class "Default")
      (node (ref "M4") (pin "30") (pinfunction "30_30") (pintype "passive"))
      (node (ref "MASTER") (pin "D49") (pinfunction "D49_D49") (pintype "bidirectional"))
      (node (ref "P_COMM") (pin "7") (pinfunction "7_7") (pintype "passive"))
    )
    (net (code "59") (name "/D50") (class "Default")
      (node (ref "M4") (pin "31") (pinfunction "31_31") (pintype "passive"))
      (node (ref "MASTER") (pin "D50") (pinfunction "D50_D50") (pintype "bidirectional"))
    )
    (net (code "60") (name "/D51") (class "Default")
      (node (ref "M4") (pin "32") (pinfunction "32_32") (pintype "passive"))
      (node (ref "MASTER") (pin "D51") (pinfunction "D51_D51") (pintype "bidirectional"))
    )
    (net (code "61") (name "/D52") (class "Default")
      (node (ref "M4") (pin "33") (pinfunction "33_33") (pintype "passive"))
      (node (ref "MASTER") (pin "D52") (pinfunction "D52_D52") (pintype "bidirectional"))
    )
    (net (code "62") (name "/D53") (class "Default")
      (node (ref "M4") (pin "34") (pinfunction "34_34") (pintype "passive"))
      (node (ref "MASTER") (pin "D53") (pinfunction "D53_D53") (pintype "bidirectional"))
    )
    (net (code "63") (name "/GND_J") (class "Default")
      (node (ref "SUPPLY") (pin "2") (pinfunction "2_2") (pintype "bidirectional"))
      (node (ref "U$35") (pin "1") (pinfunction "1_1") (pintype "bidirectional"))
    )
    (net (code "64") (name "/O1") (class "Default")
      (node (ref "D14") (pin "K") (pinfunction "C_K") (pintype "passive"))
      (node (ref "PROX_RES") (pin "2") (pinfunction "2_2") (pintype "passive"))
    )
    (net (code "65") (name "/O2") (class "Default")
      (node (ref "D1") (pin "K") (pinfunction "C_K") (pintype "passive"))
      (node (ref "PROX_RES") (pin "3") (pinfunction "3_3") (pintype "passive"))
    )
    (net (code "66") (name "/O3") (class "Default")
      (node (ref "D2") (pin "K") (pinfunction "C_K") (pintype "passive"))
      (node (ref "PROX_RES") (pin "4") (pinfunction "4_4") (pintype "passive"))
    )
    (net (code "67") (name "/O4") (class "Default")
      (node (ref "D3") (pin "K") (pinfunction "C_K") (pintype "passive"))
      (node (ref "PROX_RES") (pin "5") (pinfunction "5_5") (pintype "passive"))
    )
    (net (code "68") (name "/OUTPUT1") (class "Default")
      (node (ref "LM358") (pin "1") (pinfunction "1_1") (pintype "passive"))
      (node (ref "LM358") (pin "2") (pinfunction "2_2") (pintype "passive"))
      (node (ref "PPR1") (pin "1") (pinfunction "1_1") (pintype "passive"))
    )
    (net (code "69") (name "/OUTPUT2") (class "Default")
      (node (ref "LM358") (pin "6") (pinfunction "6_6") (pintype "passive"))
      (node (ref "LM358") (pin "7") (pinfunction "7_7") (pintype "passive"))
      (node (ref "PPR2") (pin "1") (pinfunction "1_1") (pintype "passive"))
    )
    (net (code "70") (name "/PROX1") (class "Default")
      (node (ref "P1") (pin "2") (pinfunction "2_2") (pintype "bidirectional"))
      (node (ref "U$23") (pin "1") (pinfunction "VIN_1") (pintype "bidirectional"))
    )
    (net (code "71") (name "/PROX2") (class "Default")
      (node (ref "P2") (pin "2") (pinfunction "2_2") (pintype "bidirectional"))
      (node (ref "U$24") (pin "1") (pinfunction "VIN_1") (pintype "bidirectional"))
    )
    (net (code "72") (name "/PROX3") (class "Default")
      (node (ref "P3") (pin "2") (pinfunction "2_2") (pintype "bidirectional"))
      (node (ref "U$25") (pin "1") (pinfunction "VIN_1") (pintype "bidirectional"))
    )
    (net (code "73") (name "/PROX4") (class "Default")
      (node (ref "P4") (pin "2") (pinfunction "2_2") (pintype "bidirectional"))
      (node (ref "U$26") (pin "1") (pinfunction "VIN_1") (pintype "bidirectional"))
    )
    (net (code "74") (name "/RX0") (class "Default")
      (node (ref "M2") (pin "1") (pinfunction "1_1") (pintype "passive"))
      (node (ref "MASTER") (pin "RX0") (pinfunction "RX0_RX0") (pintype "bidirectional"))
      (node (ref "U$4") (pin "RX0") (pinfunction "RX_RX0") (pintype "bidirectional"))
    )
    (net (code "75") (name "/RX1") (class "Default")
      (node (ref "M3") (pin "3") (pinfunction "3_3") (pintype "passive"))
      (node (ref "MASTER") (pin "RX1") (pinfunction "RX1_RX1") (pintype "bidirectional"))
      (node (ref "S_COMM") (pin "2") (pinfunction "2_2") (pintype "passive"))
    )
    (net (code "76") (name "/RX2") (class "Default")
      (node (ref "M3") (pin "5") (pinfunction "5_5") (pintype "passive"))
      (node (ref "MASTER") (pin "RX2") (pinfunction "RX2_RX2") (pintype "bidirectional"))
    )
    (net (code "77") (name "/RX3") (class "Default")
      (node (ref "M3") (pin "7") (pinfunction "7_7") (pintype "passive"))
      (node (ref "MASTER") (pin "RX3") (pinfunction "RX3_RX3") (pintype "bidirectional"))
    )
    (net (code "78") (name "/S-3V3") (class "Default")
      (node (ref "S7") (pin "4") (pinfunction "4_4") (pintype "passive"))
      (node (ref "SLAVE") (pin "3V3") (pinfunction "3V3_3V3") (pintype "bidirectional"))
    )
    (net (code "79") (name "/S-A0") (class "Default")
      (node (ref "S6") (pin "1") (pinfunction "1_1") (pintype "passive"))
      (node (ref "SLAVE") (pin "A0") (pinfunction "A0_A0") (pintype "bidirectional"))
    )
    (net (code "80") (name "/S-A1") (class "Default")
      (node (ref "S6") (pin "2") (pinfunction "2_2") (pintype "passive"))
      (node (ref "SLAVE") (pin "A1") (pinfunction "A1_A1") (pintype "bidirectional"))
    )
    (net (code "81") (name "/S-A2") (class "Default")
      (node (ref "S6") (pin "3") (pinfunction "3_3") (pintype "passive"))
      (node (ref "SLAVE") (pin "A2") (pinfunction "A2_A2") (pintype "bidirectional"))
    )
    (net (code "82") (name "/S-A3") (class "Default")
      (node (ref "S6") (pin "4") (pinfunction "4_4") (pintype "passive"))
      (node (ref "SLAVE") (pin "A3") (pinfunction "A3_A3") (pintype "bidirectional"))
    )
    (net (code "83") (name "/S-A4") (class "Default")
      (node (ref "S6") (pin "5") (pinfunction "5_5") (pintype "passive"))
      (node (ref "SLAVE") (pin "A4") (pinfunction "A4_A4") (pintype "bidirectional"))
    )
    (net (code "84") (name "/S-A5") (class "Default")
      (node (ref "S6") (pin "6") (pinfunction "6_6") (pintype "passive"))
      (node (ref "SLAVE") (pin "A5") (pinfunction "A5_A5") (pintype "bidirectional"))
    )
    (net (code "85") (name "/S-A6") (class "Default")
      (node (ref "S6") (pin "7") (pinfunction "7_7") (pintype "passive"))
      (node (ref "SLAVE") (pin "A6") (pinfunction "A6_A6") (pintype "bidirectional"))
    )
    (net (code "86") (name "/S-A7") (class "Default")
      (node (ref "S6") (pin "8") (pinfunction "8_8") (pintype "passive"))
      (node (ref "SLAVE") (pin "A7") (pinfunction "A7_A7") (pintype "bidirectional"))
    )
    (net (code "87") (name "/S-A8") (class "Default")
      (node (ref "S5") (pin "1") (pinfunction "1_1") (pintype "passive"))
      (node (ref "SLAVE") (pin "A8") (pinfunction "A8_A8") (pintype "bidirectional"))
    )
    (net (code "88") (name "/S-A9") (class "Default")
      (node (ref "S5") (pin "2") (pinfunction "2_2") (pintype "passive"))
      (node (ref "SLAVE") (pin "A9") (pinfunction "A9_A9") (pintype "bidirectional"))
    )
    (net (code "89") (name "/S-A10") (class "Default")
      (node (ref "S5") (pin "3") (pinfunction "3_3") (pintype "passive"))
      (node (ref "SLAVE") (pin "A10") (pinfunction "A10_A10") (pintype "bidirectional"))
    )
    (net (code "90") (name "/S-A11") (class "Default")
      (node (ref "S5") (pin "4") (pinfunction "4_4") (pintype "passive"))
      (node (ref "SLAVE") (pin "A11") (pinfunction "A11_A11") (pintype "bidirectional"))
    )
    (net (code "91") (name "/S-A12") (class "Default")
      (node (ref "S5") (pin "5") (pinfunction "5_5") (pintype "passive"))
      (node (ref "SLAVE") (pin "A12") (pinfunction "A12_A12") (pintype "bidirectional"))
    )
    (net (code "92") (name "/S-A13") (class "Default")
      (node (ref "S5") (pin "6") (pinfunction "6_6") (pintype "passive"))
      (node (ref "SLAVE") (pin "A13") (pinfunction "A13_A13") (pintype "bidirectional"))
    )
    (net (code "93") (name "/S-A14") (class "Default")
      (node (ref "S5") (pin "7") (pinfunction "7_7") (pintype "passive"))
      (node (ref "SLAVE") (pin "A14") (pinfunction "A14_A14") (pintype "bidirectional"))
    )
    (net (code "94") (name "/S-A15") (class "Default")
      (node (ref "S5") (pin "8") (pinfunction "8_8") (pintype "passive"))
      (node (ref "SLAVE") (pin "A15") (pinfunction "A15_A15") (pintype "bidirectional"))
    )
    (net (code "95") (name "/S-AREF") (class "Default")
      (node (ref "S1") (pin "8") (pinfunction "8_8") (pintype "passive"))
      (node (ref "SLAVE") (pin "AREF") (pinfunction "AREF_AREF") (pintype "bidirectional"))
    )
    (net (code "96") (name "/S-D2") (class "Default")
      (node (ref "E_SLAVE1") (pin "3") (pinfunction "3_3") (pintype "bidirectional"))
      (node (ref "PULL_SLAVE") (pin "4") (pinfunction "4_4") (pintype "passive"))
      (node (ref "S2") (pin "3") (pinfunction "3_3") (pintype "passive"))
      (node (ref "SLAVE") (pin "D2") (pinfunction "D2_D2") (pintype "bidirectional"))
    )
    (net (code "97") (name "/S-D3") (class "Default")
      (node (ref "E_SLAVE2") (pin "3") (pinfunction "3_3") (pintype "bidirectional"))
      (node (ref "PULL_SLAVE") (pin "2") (pinfunction "2_2") (pintype "passive"))
      (node (ref "S2") (pin "4") (pinfunction "4_4") (pintype "passive"))
      (node (ref "SLAVE") (pin "D3") (pinfunction "D3_D3") (pintype "bidirectional"))
    )
    (net (code "98") (name "/S-D4") (class "Default")
      (node (ref "S2") (pin "5") (pinfunction "5_5") (pintype "passive"))
      (node (ref "SLAVE") (pin "D4") (pinfunction "D4_D4") (pintype "bidirectional"))
    )
    (net (code "99") (name "/S-D5") (class "Default")
      (node (ref "S2") (pin "6") (pinfunction "6_6") (pintype "passive"))
      (node (ref "SLAVE") (pin "D5") (pinfunction "D5_D5") (pintype "bidirectional"))
    )
    (net (code "100") (name "/S-D6") (class "Default")
      (node (ref "S2") (pin "7") (pinfunction "7_7") (pintype "passive"))
      (node (ref "SLAVE") (pin "D6") (pinfunction "D6_D6") (pintype "bidirectional"))
    )
    (net (code "101") (name "/S-D7") (class "Default")
      (node (ref "R1") (pin "2") (pinfunction "2_2") (pintype "passive"))
      (node (ref "S2") (pin "8") (pinfunction "8_8") (pintype "passive"))
      (node (ref "SLAVE") (pin "D7") (pinfunction "D7_D7") (pintype "bidirectional"))
    )
    (net (code "102") (name "/S-D8") (class "Default")
      (node (ref "S1") (pin "1") (pinfunction "1_1") (pintype "passive"))
      (node (ref "SLAVE") (pin "D8") (pinfunction "D8_D8") (pintype "bidirectional"))
    )
    (net (code "103") (name "/S-D9") (class "Default")
      (node (ref "S1") (pin "2") (pinfunction "2_2") (pintype "passive"))
      (node (ref "SLAVE") (pin "D9") (pinfunction "D9_D9") (pintype "bidirectional"))
    )
    (net (code "104") (name "/S-D10") (class "Default")
      (node (ref "S1") (pin "3") (pinfunction "3_3") (pintype "passive"))
      (node (ref "SLAVE") (pin "D10") (pinfunction "D10_D10") (pintype "bidirectional"))
    )
    (net (code "105") (name "/S-D11") (class "Default")
      (node (ref "S1") (pin "4") (pinfunction "4_4") (pintype "passive"))
      (node (ref "SLAVE") (pin "D11") (pinfunction "D11_D11") (pintype "bidirectional"))
    )
    (net (code "106") (name "/S-D12") (class "Default")
      (node (ref "S1") (pin "5") (pinfunction "5_5") (pintype "passive"))
      (node (ref "SLAVE") (pin "D12") (pinfunction "D12_D12") (pintype "bidirectional"))
    )
    (net (code "107") (name "/S-D13") (class "Default")
      (node (ref "S1") (pin "6") (pinfunction "6_6") (pintype "passive"))
      (node (ref "SLAVE") (pin "D13") (pinfunction "D13_D13") (pintype "bidirectional"))
    )
    (net (code "108") (name "/S-D22") (class "Default")
      (node (ref "E_SLAVE1") (pin "2") (pinfunction "2_2") (pintype "bidirectional"))
      (node (ref "PULL_SLAVE") (pin "5") (pinfunction "5_5") (pintype "passive"))
      (node (ref "S-4") (pin "3") (pinfunction "3_3") (pintype "passive"))
      (node (ref "SLAVE") (pin "D22") (pinfunction "D22_D22") (pintype "bidirectional"))
    )
    (net (code "109") (name "/S-D23") (class "Default")
      (node (ref "E_SLAVE2") (pin "2") (pinfunction "2_2") (pintype "bidirectional"))
      (node (ref "PULL_SLAVE") (pin "3") (pinfunction "3_3") (pintype "passive"))
      (node (ref "S-4") (pin "4") (pinfunction "4_4") (pintype "passive"))
      (node (ref "SLAVE") (pin "D23") (pinfunction "D23_D23") (pintype "bidirectional"))
    )
    (net (code "110") (name "/S-D24") (class "Default")
      (node (ref "D2") (pin "A") (pinfunction "A_A") (pintype "passive"))
      (node (ref "S-4") (pin "5") (pinfunction "5_5") (pintype "passive"))
      (node (ref "SLAVE") (pin "D24") (pinfunction "D24_D24") (pintype "bidirectional"))
      (node (ref "U$25") (pin "3") (pinfunction "VO_3") (pintype "bidirectional"))
    )
    (net (code "111") (name "/S-D25") (class "Default")
      (node (ref "D3") (pin "A") (pinfunction "A_A") (pintype "passive"))
      (node (ref "S-4") (pin "6") (pinfunction "6_6") (pintype "passive"))
      (node (ref "SLAVE") (pin "D25") (pinfunction "D25_D25") (pintype "bidirectional"))
      (node (ref "U$26") (pin "3") (pinfunction "VO_3") (pintype "bidirectional"))
    )
    (net (code "112") (name "/S-D26") (class "Default")
      (node (ref "P_COMM") (pin "16") (pinfunction "16_16") (pintype "passive"))
      (node (ref "S-4") (pin "7") (pinfunction "7_7") (pintype "passive"))
      (node (ref "SLAVE") (pin "D26") (pinfunction "D26_D26") (pintype "bidirectional"))
    )
    (net (code "113") (name "/S-D27") (class "Default")
      (node (ref "P_COMM") (pin "15") (pinfunction "15_15") (pintype "passive"))
      (node (ref "S-4") (pin "8") (pinfunction "8_8") (pintype "passive"))
      (node (ref "SLAVE") (pin "D27") (pinfunction "D27_D27") (pintype "bidirectional"))
    )
    (net (code "114") (name "/S-D28") (class "Default")
      (node (ref "P_COMM") (pin "12") (pinfunction "12_12") (pintype "passive"))
      (node (ref "S-4") (pin "9") (pinfunction "9_9") (pintype "passive"))
      (node (ref "SLAVE") (pin "D28") (pinfunction "D28_D28") (pintype "bidirectional"))
    )
    (net (code "115") (name "/S-D29") (class "Default")
      (node (ref "P_COMM") (pin "11") (pinfunction "11_11") (pintype "passive"))
      (node (ref "S-4") (pin "10") (pinfunction "10_10") (pintype "passive"))
      (node (ref "SLAVE") (pin "D29") (pinfunction "D29_D29") (pintype "bidirectional"))
    )
    (net (code "116") (name "/S-D30") (class "Default")
      (node (ref "P_COMM") (pin "10") (pinfunction "10_10") (pintype "passive"))
      (node (ref "S-4") (pin "11") (pinfunction "11_11") (pintype "passive"))
      (node (ref "SLAVE") (pin "D30") (pinfunction "D30_D30") (pintype "bidirectional"))
    )
    (net (code "117") (name "/S-D31") (class "Default")
      (node (ref "S-4") (pin "12") (pinfunction "12_12") (pintype "passive"))
      (node (ref "SLAVE") (pin "D31") (pinfunction "D31_D31") (pintype "bidirectional"))
    )
    (net (code "118") (name "/S-D32") (class "Default")
      (node (ref "S-4") (pin "13") (pinfunction "13_13") (pintype "passive"))
      (node (ref "SLAVE") (pin "D32") (pinfunction "D32_D32") (pintype "bidirectional"))
    )
    (net (code "119") (name "/S-D33") (class "Default")
      (node (ref "S-4") (pin "14") (pinfunction "14_14") (pintype "passive"))
      (node (ref "SLAVE") (pin "D33") (pinfunction "D33_D33") (pintype "bidirectional"))
    )
    (net (code "120") (name "/S-D34") (class "Default")
      (node (ref "S-4") (pin "15") (pinfunction "15_15") (pintype "passive"))
      (node (ref "SLAVE") (pin "D34") (pinfunction "D34_D34") (pintype "bidirectional"))
    )
    (net (code "121") (name "/S-D35") (class "Default")
      (node (ref "S-4") (pin "16") (pinfunction "16_16") (pintype "passive"))
      (node (ref "SLAVE") (pin "D35") (pinfunction "D35_D35") (pintype "bidirectional"))
    )
    (net (code "122") (name "/S-D36") (class "Default")
      (node (ref "S-4") (pin "17") (pinfunction "17_17") (pintype "passive"))
      (node (ref "SLAVE") (pin "D36") (pinfunction "D36_D36") (pintype "bidirectional"))
    )
    (net (code "123") (name "/S-D37") (class "Default")
      (node (ref "S-4") (pin "18") (pinfunction "18_18") (pintype "passive"))
      (node (ref "SLAVE") (pin "D37") (pinfunction "D37_D37") (pintype "bidirectional"))
    )
    (net (code "124") (name "/S-D38") (class "Default")
      (node (ref "R8") (pin "2") (pinfunction "2_2") (pintype "passive"))
      (node (ref "S-4") (pin "19") (pinfunction "19_19") (pintype "passive"))
      (node (ref "SLAVE") (pin "D38") (pinfunction "D38_D38") (pintype "bidirectional"))
    )
    (net (code "125") (name "/S-D39") (class "Default")
      (node (ref "R9") (pin "2") (pinfunction "2_2") (pintype "passive"))
      (node (ref "S-4") (pin "20") (pinfunction "20_20") (pintype "passive"))
      (node (ref "SLAVE") (pin "D39") (pinfunction "D39_D39") (pintype "bidirectional"))
    )
    (net (code "126") (name "/S-D40") (class "Default")
      (node (ref "R10") (pin "2") (pinfunction "2_2") (pintype "passive"))
      (node (ref "S-4") (pin "21") (pinfunction "21_21") (pintype "passive"))
      (node (ref "SLAVE") (pin "D40") (pinfunction "D40_D40") (pintype "bidirectional"))
    )
    (net (code "127") (name "/S-D41") (class "Default")
      (node (ref "BUZ2") (pin "2") (pinfunction "2_2") (pintype "passive"))
      (node (ref "S-4") (pin "22") (pinfunction "22_22") (pintype "passive"))
      (node (ref "SLAVE") (pin "D41") (pinfunction "D41_D41") (pintype "bidirectional"))
    )
    (net (code "128") (name "/S-D42") (class "Default")
      (node (ref "S-4") (pin "23") (pinfunction "23_23") (pintype "passive"))
      (node (ref "SLAVE") (pin "D42") (pinfunction "D42_D42") (pintype "bidirectional"))
    )
    (net (code "129") (name "/S-D43") (class "Default")
      (node (ref "S-4") (pin "24") (pinfunction "24_24") (pintype "passive"))
      (node (ref "SLAVE") (pin "D43") (pinfunction "D43_D43") (pintype "bidirectional"))
    )
    (net (code "130") (name "/S-D44") (class "Default")
      (node (ref "S-4") (pin "25") (pinfunction "25_25") (pintype "passive"))
      (node (ref "SLAVE") (pin "D44") (pinfunction "D44_D44") (pintype "bidirectional"))
    )
    (net (code "131") (name "/S-D45") (class "Default")
      (node (ref "S-4") (pin "26") (pinfunction "26_26") (pintype "passive"))
      (node (ref "SLAVE") (pin "D45") (pinfunction "D45_D45") (pintype "bidirectional"))
    )
    (net (code "132") (name "/S-D46") (class "Default")
      (node (ref "S-4") (pin "27") (pinfunction "27_27") (pintype "passive"))
      (node (ref "SLAVE") (pin "D46") (pinfunction "D46_D46") (pintype "bidirectional"))
    )
    (net (code "133") (name "/S-D47") (class "Default")
      (node (ref "S-4") (pin "28") (pinfunction "28_28") (pintype "passive"))
      (node (ref "SLAVE") (pin "D47") (pinfunction "D47_D47") (pintype "bidirectional"))
    )
    (net (code "134") (name "/S-D48") (class "Default")
      (node (ref "S-4") (pin "29") (pinfunction "29_29") (pintype "passive"))
      (node (ref "SLAVE") (pin "D48") (pinfunction "D48_D48") (pintype "bidirectional"))
    )
    (net (code "135") (name "/S-D49") (class "Default")
      (node (ref "S-4") (pin "30") (pinfunction "30_30") (pintype "passive"))
      (node (ref "SLAVE") (pin "D49") (pinfunction "D49_D49") (pintype "bidirectional"))
    )
    (net (code "136") (name "/S-D50") (class "Default")
      (node (ref "P_COMM") (pin "9") (pinfunction "9_9") (pintype "passive"))
      (node (ref "S-4") (pin "31") (pinfunction "31_31") (pintype "passive"))
      (node (ref "SLAVE") (pin "D50") (pinfunction "D50_D50") (pintype "bidirectional"))
    )
    (net (code "137") (name "/S-D51") (class "Default")
      (node (ref "P_COMM") (pin "13") (pinfunction "13_13") (pintype "passive"))
      (node (ref "S-4") (pin "32") (pinfunction "32_32") (pintype "passive"))
      (node (ref "SLAVE") (pin "D51") (pinfunction "D51_D51") (pintype "bidirectional"))
    )
    (net (code "138") (name "/S-D52") (class "Default")
      (node (ref "P_COMM") (pin "14") (pinfunction "14_14") (pintype "passive"))
      (node (ref "S-4") (pin "33") (pinfunction "33_33") (pintype "passive"))
      (node (ref "SLAVE") (pin "D52") (pinfunction "D52_D52") (pintype "bidirectional"))
    )
    (net (code "139") (name "/S-D53") (class "Default")
      (node (ref "S-4") (pin "34") (pinfunction "34_34") (pintype "passive"))
      (node (ref "SLAVE") (pin "D53") (pinfunction "D53_D53") (pintype "bidirectional"))
    )
    (net (code "140") (name "/S-RX0") (class "Default")
      (node (ref "S2") (pin "1") (pinfunction "1_1") (pintype "passive"))
      (node (ref "SLAVE") (pin "RX0") (pinfunction "RX0_RX0") (pintype "bidirectional"))
    )
    (net (code "141") (name "/S-RX1") (class "Default")
      (node (ref "S-3") (pin "3") (pinfunction "3_3") (pintype "passive"))
      (node (ref "SLAVE") (pin "RX1") (pinfunction "RX1_RX1") (pintype "bidirectional"))
      (node (ref "S_COMM") (pin "4") (pinfunction "4_4") (pintype "passive"))
    )
    (net (code "142") (name "/S-RX2") (class "Default")
      (node (ref "S-3") (pin "5") (pinfunction "5_5") (pintype "passive"))
      (node (ref "SLAVE") (pin "RX2") (pinfunction "RX2_RX2") (pintype "bidirectional"))
    )
    (net (code "143") (name "/S-RX3") (class "Default")
      (node (ref "S-3") (pin "7") (pinfunction "7_7") (pintype "passive"))
      (node (ref "SLAVE") (pin "RX3") (pinfunction "RX3_RX3") (pintype "bidirectional"))
    )
    (net (code "144") (name "/S-TX0") (class "Default")
      (node (ref "S2") (pin "2") (pinfunction "2_2") (pintype "passive"))
      (node (ref "SLAVE") (pin "TX0") (pinfunction "TX0_TX0") (pintype "bidirectional"))
    )
    (net (code "145") (name "/S-TX1") (class "Default")
      (node (ref "S-3") (pin "4") (pinfunction "4_4") (pintype "passive"))
      (node (ref "SLAVE") (pin "TX1") (pinfunction "TX1_TX1") (pintype "bidirectional"))
      (node (ref "S_COMM") (pin "3") (pinfunction "3_3") (pintype "passive"))
    )
    (net (code "146") (name "/S-TX2") (class "Default")
      (node (ref "S-3") (pin "6") (pinfunction "6_6") (pintype "passive"))
      (node (ref "SLAVE") (pin "TX2") (pinfunction "TX2_TX2") (pintype "bidirectional"))
    )
    (net (code "147") (name "/S-TX3") (class "Default")
      (node (ref "S-3") (pin "8") (pinfunction "8_8") (pintype "passive"))
      (node (ref "SLAVE") (pin "TX3") (pinfunction "TX3_TX3") (pintype "bidirectional"))
    )
    (net (code "148") (name "/TX0") (class "Default")
      (node (ref "M2") (pin "2") (pinfunction "2_2") (pintype "passive"))
      (node (ref "MASTER") (pin "TX0") (pinfunction "TX0_TX0") (pintype "bidirectional"))
      (node (ref "U$4") (pin "TX0") (pinfunction "TX_TX0") (pintype "bidirectional"))
    )
    (net (code "149") (name "/TX1") (class "Default")
      (node (ref "M3") (pin "4") (pinfunction "4_4") (pintype "passive"))
      (node (ref "MASTER") (pin "TX1") (pinfunction "TX1_TX1") (pintype "bidirectional"))
      (node (ref "S_COMM") (pin "1") (pinfunction "1_1") (pintype "passive"))
    )
    (net (code "150") (name "/TX2") (class "Default")
      (node (ref "M3") (pin "6") (pinfunction "6_6") (pintype "passive"))
      (node (ref "MASTER") (pin "TX2") (pinfunction "TX2_TX2") (pintype "bidirectional"))
      (node (ref "SABER1") (pin "3") (pinfunction "3_3") (pintype "bidirectional"))
    )
    (net (code "151") (name "/TX3") (class "Default")
      (node (ref "M3") (pin "8") (pinfunction "8_8") (pintype "passive"))
      (node (ref "MASTER") (pin "TX3") (pinfunction "TX3_TX3") (pintype "bidirectional"))
      (node (ref "SABER2") (pin "3") (pinfunction "3_3") (pintype "bidirectional"))
    )
    (net (code "152") (name "/U1") (class "Default")
      (node (ref "D10") (pin "K") (pinfunction "C_K") (pintype "passive"))
      (node (ref "ULN") (pin "12") (pinfunction "12_12") (pintype "passive"))
      (node (ref "ULN2") (pin "1") (pinfunction "1_1") (pintype "bidirectional"))
    )
    (net (code "153") (name "/U2") (class "Default")
      (node (ref "D9") (pin "K") (pinfunction "C_K") (pintype "passive"))
      (node (ref "ULN") (pin "13") (pinfunction "13_13") (pintype "passive"))
      (node (ref "ULN2") (pin "2") (pinfunction "2_2") (pintype "bidirectional"))
    )
    (net (code "154") (name "/U3") (class "Default")
      (node (ref "D8") (pin "K") (pinfunction "C_K") (pintype "passive"))
      (node (ref "ULN") (pin "14") (pinfunction "14_14") (pintype "passive"))
      (node (ref "ULN2") (pin "3") (pinfunction "3_3") (pintype "bidirectional"))
    )
    (net (code "155") (name "/U4") (class "Default")
      (node (ref "D7") (pin "K") (pinfunction "C_K") (pintype "passive"))
      (node (ref "ULN") (pin "15") (pinfunction "15_15") (pintype "passive"))
      (node (ref "ULN1") (pin "1") (pinfunction "1_1") (pintype "bidirectional"))
    )
    (net (code "156") (name "/U5") (class "Default")
      (node (ref "D6") (pin "K") (pinfunction "C_K") (pintype "passive"))
      (node (ref "ULN") (pin "16") (pinfunction "16_16") (pintype "passive"))
      (node (ref "ULN1") (pin "2") (pinfunction "2_2") (pintype "bidirectional"))
    )
    (net (code "157") (name "/VIN") (class "Default")
      (node (ref "M7") (pin "8") (pinfunction "8_8") (pintype "passive"))
      (node (ref "MASTER") (pin "VIN") (pinfunction "VIN_VIN") (pintype "bidirectional"))
      (node (ref "S7") (pin "8") (pinfunction "8_8") (pintype "passive"))
      (node (ref "SERVO") (pin "2") (pinfunction "2_2") (pintype "bidirectional"))
      (node (ref "SLAVE") (pin "VIN") (pinfunction "VIN_VIN") (pintype "bidirectional"))
      (node (ref "U$3") (pin "OUT+") (pinfunction "OUT+_OUT+") (pintype "bidirectional"))
      (node (ref "U$4") (pin "VIN") (pinfunction "VIN_VIN") (pintype "bidirectional"))
      (node (ref "U2") (pin "3") (pinfunction "VIN_3") (pintype "input"))
    )
    (net (code "158") (name "/VREF") (class "Default")
      (node (ref "M7") (pin "2") (pinfunction "2_2") (pintype "passive"))
      (node (ref "MASTER") (pin "IOREF") (pinfunction "IOREF_IOREF") (pintype "bidirectional"))
      (node (ref "U$4") (pin "VREF") (pinfunction "VREF_VREF") (pintype "bidirectional"))
    )
    (net (code "159") (name "5V") (class "Default")
      (node (ref "5V") (pin "3") (pinfunction "3_3") (pintype "passive"))
      (node (ref "5V") (pin "4") (pinfunction "4_4") (pintype "passive"))
      (node (ref "E_MASTER1") (pin "5") (pinfunction "5_5") (pintype "bidirectional"))
      (node (ref "E_MASTER2") (pin "5") (pinfunction "5_5") (pintype "bidirectional"))
      (node (ref "E_SLAVE1") (pin "5") (pinfunction "5_5") (pintype "bidirectional"))
      (node (ref "E_SLAVE2") (pin "5") (pinfunction "5_5") (pintype "bidirectional"))
      (node (ref "IMU_BLOCK2") (pin "4") (pinfunction "4_4") (pintype "bidirectional"))
      (node (ref "IMU_BLOCK4") (pin "4") (pinfunction "4_4") (pintype "bidirectional"))
      (node (ref "PULL_MASTER") (pin "1") (pinfunction "1_1") (pintype "passive"))
      (node (ref "PULL_SLAVE") (pin "1") (pinfunction "1_1") (pintype "passive"))
      (node (ref "RN3") (pin "1") (pinfunction "1_1") (pintype "passive"))
      (node (ref "SWITCH") (pin "1") (pinfunction "1_1") (pintype "bidirectional"))
      (node (ref "U2") (pin "2") (pinfunction "VOUT_2") (pintype "output"))
      (node (ref "U2") (pin "4") (pinfunction "VOUT_4") (pintype "output"))
    )
    (net (code "160") (name "5VA") (class "Default")
      (node (ref "5V") (pin "1") (pinfunction "1_1") (pintype "passive"))
      (node (ref "5V_ARRAY") (pin "1") (pinfunction "1_1") (pintype "passive"))
      (node (ref "5V_ARRAY") (pin "2") (pinfunction "2_2") (pintype "passive"))
      (node (ref "5V_ARRAY") (pin "3") (pinfunction "3_3") (pintype "passive"))
      (node (ref "5V_ARRAY") (pin "4") (pinfunction "4_4") (pintype "passive"))
      (node (ref "5V_ARRAY") (pin "5") (pinfunction "5_5") (pintype "passive"))
      (node (ref "I2C1P") (pin "1") (pinfunction "1_1") (pintype "passive"))
      (node (ref "IMU_MASTER") (pin "4") (pinfunction "4_4") (pintype "bidirectional"))
      (node (ref "M4") (pin "1") (pinfunction "1_1") (pintype "passive"))
      (node (ref "M4") (pin "2") (pinfunction "2_2") (pintype "passive"))
      (node (ref "M7") (pin "5") (pinfunction "5_5") (pintype "passive"))
      (node (ref "MASTER") (pin "5V") (pinfunction "5V_5V") (pintype "bidirectional"))
      (node (ref "MASTER") (pin "5V1") (pinfunction "5V1_5V1") (pintype "bidirectional"))
      (node (ref "MASTER") (pin "5V2") (pinfunction "5V2_5V2") (pintype "bidirectional"))
      (node (ref "MASTER") (pin "5V3") (pinfunction "5V3_5V3") (pintype "bidirectional"))
      (node (ref "U$4") (pin "5V") (pinfunction "5V_5V") (pintype "bidirectional"))
      (node (ref "U$4") (pin "5V1") (pinfunction "5V1_5V1") (pintype "bidirectional"))
    )
    (net (code "161") (name "GND") (class "Default")
      (node (ref "BUZZER") (pin "-") (pinfunction "2_-") (pintype "passive"))
      (node (ref "C1") (pin "2") (pinfunction "-_2") (pintype "passive"))
      (node (ref "C2") (pin "2") (pinfunction "-_2") (pintype "passive"))
      (node (ref "E_MASTER1") (pin "1") (pinfunction "1_1") (pintype "bidirectional"))
      (node (ref "E_MASTER1") (pin "4") (pinfunction "4_4") (pintype "bidirectional"))
      (node (ref "E_MASTER2") (pin "1") (pinfunction "1_1") (pintype "bidirectional"))
      (node (ref "E_MASTER2") (pin "4") (pinfunction "4_4") (pintype "bidirectional"))
      (node (ref "E_SLAVE1") (pin "1") (pinfunction "1_1") (pintype "bidirectional"))
      (node (ref "E_SLAVE1") (pin "4") (pinfunction "4_4") (pintype "bidirectional"))
      (node (ref "E_SLAVE2") (pin "1") (pinfunction "1_1") (pintype "bidirectional"))
      (node (ref "E_SLAVE2") (pin "4") (pinfunction "4_4") (pintype "bidirectional"))
      (node (ref "GND_ARRAY") (pin "1") (pinfunction "1_1") (pintype "passive"))
      (node (ref "GND_ARRAY") (pin "2") (pinfunction "2_2") (pintype "passive"))
      (node (ref "GND_ARRAY") (pin "3") (pinfunction "3_3") (pintype "passive"))
      (node (ref "GND_ARRAY") (pin "4") (pinfunction "4_4") (pintype "passive"))
      (node (ref "GND_ARRAY") (pin "5") (pinfunction "5_5") (pintype "passive"))
      (node (ref "IMU_BLOCK2") (pin "3") (pinfunction "3_3") (pintype "bidirectional"))
      (node (ref "IMU_BLOCK3") (pin "3") (pinfunction "3_3") (pintype "bidirectional"))
      (node (ref "IMU_BLOCK4") (pin "3") (pinfunction "3_3") (pintype "bidirectional"))
      (node (ref "IMU_MASTER") (pin "3") (pinfunction "3_3") (pintype "bidirectional"))
      (node (ref "LIMIT_SWITCH") (pin "3") (pinfunction "3_3") (pintype "bidirectional"))
      (node (ref "LM358") (pin "4") (pinfunction "4_4") (pintype "passive"))
      (node (ref "M1") (pin "7") (pinfunction "7_7") (pintype "passive"))
      (node (ref "M4") (pin "35") (pinfunction "35_35") (pintype "passive"))
      (node (ref "M4") (pin "36") (pinfunction "36_36") (pintype "passive"))
      (node (ref "M7") (pin "6") (pinfunction "6_6") (pintype "passive"))
      (node (ref "M7") (pin "7") (pinfunction "7_7") (pintype "passive"))
      (node (ref "MASTER") (pin "GD3") (pinfunction "GD3_GD3") (pintype "bidirectional"))
      (node (ref "MASTER") (pin "GD4") (pinfunction "GD4_GD4") (pintype "bidirectional"))
      (node (ref "MASTER") (pin "GND") (pinfunction "GND_GND") (pintype "bidirectional"))
      (node (ref "MASTER") (pin "GND1") (pinfunction "GND1_GND1") (pintype "bidirectional"))
      (node (ref "MASTER") (pin "GND2") (pinfunction "GND2_GND2") (pintype "bidirectional"))
      (node (ref "MASTER") (pin "GND5") (pinfunction "GND5_GND5") (pintype "bidirectional"))
      (node (ref "ODRIVE") (pin "1") (pinfunction "1_1") (pintype "passive"))
      (node (ref "P1") (pin "1") (pinfunction "1_1") (pintype "bidirectional"))
      (node (ref "P2") (pin "1") (pinfunction "1_1") (pintype "bidirectional"))
      (node (ref "P3") (pin "1") (pinfunction "1_1") (pintype "bidirectional"))
      (node (ref "P4") (pin "1") (pinfunction "1_1") (pintype "bidirectional"))
      (node (ref "PROX_RES") (pin "1") (pinfunction "1_1") (pintype "passive"))
      (node (ref "RST_SWITCH") (pin "2") (pinfunction "2_2") (pintype "passive"))
      (node (ref "S-4") (pin "35") (pinfunction "35_35") (pintype "passive"))
      (node (ref "S-4") (pin "36") (pinfunction "36_36") (pintype "passive"))
      (node (ref "S-ICSP") (pin "5") (pinfunction "5_5") (pintype "passive"))
      (node (ref "S1") (pin "7") (pinfunction "7_7") (pintype "passive"))
      (node (ref "S7") (pin "6") (pinfunction "6_6") (pintype "passive"))
      (node (ref "S7") (pin "7") (pinfunction "7_7") (pintype "passive"))
      (node (ref "SABER1") (pin "1") (pinfunction "1_1") (pintype "bidirectional"))
      (node (ref "SABER2") (pin "1") (pinfunction "1_1") (pintype "bidirectional"))
      (node (ref "SERVO") (pin "3") (pinfunction "3_3") (pintype "bidirectional"))
      (node (ref "SLAVE") (pin "GD3") (pinfunction "GD3_GD3") (pintype "bidirectional"))
      (node (ref "SLAVE") (pin "GD4") (pinfunction "GD4_GD4") (pintype "bidirectional"))
      (node (ref "SLAVE") (pin "GND") (pinfunction "GND_GND") (pintype "bidirectional"))
      (node (ref "SLAVE") (pin "GND1") (pinfunction "GND1_GND1") (pintype "bidirectional"))
      (node (ref "SLAVE") (pin "GND2") (pinfunction "GND2_GND2") (pintype "bidirectional"))
      (node (ref "SLAVE") (pin "GND5") (pinfunction "GND5_GND5") (pintype "bidirectional"))
      (node (ref "SWITCH") (pin "2") (pinfunction "2_2") (pintype "bidirectional"))
      (node (ref "U$23") (pin "2") (pinfunction "GND_2") (pintype "bidirectional"))
      (node (ref "U$24") (pin "2") (pinfunction "GND_2") (pintype "bidirectional"))
      (node (ref "U$25") (pin "2") (pinfunction "GND_2") (pintype "bidirectional"))
      (node (ref "U$26") (pin "2") (pinfunction "GND_2") (pintype "bidirectional"))
      (node (ref "U$3") (pin "IN-") (pinfunction "IN-_IN-") (pintype "bidirectional"))
      (node (ref "U$3") (pin "OUT-") (pinfunction "OUT-_OUT-") (pintype "bidirectional"))
      (node (ref "U$35") (pin "2") (pinfunction "2_2") (pintype "bidirectional"))
      (node (ref "U$4") (pin "GND") (pinfunction "GND_GND") (pintype "bidirectional"))
      (node (ref "U$4") (pin "GND1") (pinfunction "GD_GND1") (pintype "bidirectional"))
      (node (ref "U$4") (pin "GND2") (pinfunction "GND2_GND2") (pintype "bidirectional"))
      (node (ref "U$4") (pin "GND3") (pinfunction "GND3_GND3") (pintype "bidirectional"))
      (node (ref "U2") (pin "1") (pinfunction "ADJ/GND_1") (pintype "power_in"))
      (node (ref "ULN") (pin "8") (pinfunction "8_8") (pintype "passive"))
      (node (ref "VCC-GND") (pin "2") (pinfunction "2_2") (pintype "bidirectional"))
    )
    (net (code "162") (name "MISO") (class "Default")
      (node (ref "MASTER") (pin "MISO") (pinfunction "MISO_MISO") (pintype "bidirectional"))
      (node (ref "U$4") (pin "MISO") (pinfunction "MI_MISO") (pintype "bidirectional"))
    )
    (net (code "163") (name "MOSI") (class "Default")
      (node (ref "MASTER") (pin "MOSI") (pinfunction "MOSI_MOSI") (pintype "bidirectional"))
      (node (ref "U$4") (pin "MOSI") (pinfunction "MO_MOSI") (pintype "bidirectional"))
    )
    (net (code "164") (name "Net-(BUZZER-1)") (class "Default")
      (node (ref "BUZ1") (pin "1") (pinfunction "1_1") (pintype "passive"))
      (node (ref "BUZ2") (pin "1") (pinfunction "1_1") (pintype "passive"))
      (node (ref "BUZZER") (pin "+") (pinfunction "1_+") (pintype "passive"))
    )
    (net (code "165") (name "Net-(C1-+)") (class "Default")
      (node (ref "C1") (pin "1") (pinfunction "+_1") (pintype "passive"))
      (node (ref "LM358") (pin "5") (pinfunction "5_5") (pintype "passive"))
      (node (ref "R1") (pin "1") (pinfunction "1_1") (pintype "passive"))
    )
    (net (code "166") (name "Net-(C2-+)") (class "Default")
      (node (ref "C2") (pin "1") (pinfunction "+_1") (pintype "passive"))
      (node (ref "LM358") (pin "3") (pinfunction "3_3") (pintype "passive"))
      (node (ref "R3") (pin "2") (pinfunction "2_2") (pintype "passive"))
    )
    (net (code "167") (name "Net-(D6-PadA)") (class "Default")
      (node (ref "D6") (pin "A") (pinfunction "A_A") (pintype "passive"))
      (node (ref "RN3") (pin "2") (pinfunction "2_2") (pintype "passive"))
    )
    (net (code "168") (name "Net-(D7-PadA)") (class "Default")
      (node (ref "D7") (pin "A") (pinfunction "A_A") (pintype "passive"))
      (node (ref "RN3") (pin "3") (pinfunction "3_3") (pintype "passive"))
    )
    (net (code "169") (name "Net-(D8-PadA)") (class "Default")
      (node (ref "D8") (pin "A") (pinfunction "A_A") (pintype "passive"))
      (node (ref "RN3") (pin "4") (pinfunction "4_4") (pintype "passive"))
    )
    (net (code "170") (name "Net-(D9-PadA)") (class "Default")
      (node (ref "D9") (pin "A") (pinfunction "A_A") (pintype "passive"))
      (node (ref "RN3") (pin "5") (pinfunction "5_5") (pintype "passive"))
    )
    (net (code "171") (name "Net-(D10-PadA)") (class "Default")
      (node (ref "D10") (pin "A") (pinfunction "A_A") (pintype "passive"))
      (node (ref "RN3") (pin "6") (pinfunction "6_6") (pintype "passive"))
    )
    (net (code "172") (name "Net-(DEBUG-S-Pad1)") (class "Default")
      (node (ref "DEBUG-S") (pin "1") (pinfunction "1_1") (pintype "bidirectional"))
      (node (ref "R10") (pin "1") (pinfunction "1_1") (pintype "passive"))
    )
    (net (code "173") (name "Net-(DEBUG-S-Pad2)") (class "Default")
      (node (ref "DEBUG-S") (pin "2") (pinfunction "2_2") (pintype "bidirectional"))
      (node (ref "R9") (pin "1") (pinfunction "1_1") (pintype "passive"))
    )
    (net (code "174") (name "Net-(DEBUG-S-Pad3)") (class "Default")
      (node (ref "DEBUG-S") (pin "3") (pinfunction "3_3") (pintype "bidirectional"))
      (node (ref "R8") (pin "1") (pinfunction "1_1") (pintype "passive"))
    )
    (net (code "175") (name "Net-(DEBUG_M-Pad1)") (class "Default")
      (node (ref "DEBUG_M") (pin "1") (pinfunction "1_1") (pintype "bidirectional"))
      (node (ref "R2") (pin "1") (pinfunction "1_1") (pintype "passive"))
    )
    (net (code "176") (name "Net-(DEBUG_M-Pad2)") (class "Default")
      (node (ref "DEBUG_M") (pin "2") (pinfunction "2_2") (pintype "bidirectional"))
      (node (ref "R4") (pin "1") (pinfunction "1_1") (pintype "passive"))
    )
    (net (code "177") (name "Net-(DEBUG_M-Pad3)") (class "Default")
      (node (ref "DEBUG_M") (pin "3") (pinfunction "3_3") (pintype "bidirectional"))
      (node (ref "R5") (pin "1") (pinfunction "1_1") (pintype "passive"))
    )
    (net (code "178") (name "Net-(DEBUG_M-Pad4)") (class "Default")
      (node (ref "DEBUG_M") (pin "4") (pinfunction "4_4") (pintype "bidirectional"))
      (node (ref "R6") (pin "1") (pinfunction "1_1") (pintype "passive"))
    )
    (net (code "179") (name "Net-(DEBUG_M-Pad5)") (class "Default")
      (node (ref "DEBUG_M") (pin "5") (pinfunction "5_5") (pintype "bidirectional"))
      (node (ref "R7") (pin "1") (pinfunction "1_1") (pintype "passive"))
    )
    (net (code "180") (name "Net-(M7-Pad1)") (class "Default")
      (node (ref "M7") (pin "1") (pinfunction "1_1") (pintype "passive"))
      (node (ref "MASTER") (pin "-") (pinfunction "-_-") (pintype "bidirectional"))
    )
    (net (code "181") (name "Net-(RESET-Pad3)") (class "Default")
      (node (ref "RESET") (pin "3") (pinfunction "3_3") (pintype "passive"))
      (node (ref "RESET") (pin "4") (pinfunction "4_4") (pintype "passive"))
      (node (ref "RST_SWITCH") (pin "1") (pinfunction "1_1") (pintype "passive"))
    )
    (net (code "182") (name "Net-(S7-Pad1)") (class "Default")
      (node (ref "S7") (pin "1") (pinfunction "1_1") (pintype "passive"))
      (node (ref "SLAVE") (pin "-") (pinfunction "-_-") (pintype "bidirectional"))
    )
    (net (code "183") (name "Net-(S7-Pad2)") (class "Default")
      (node (ref "S7") (pin "2") (pinfunction "2_2") (pintype "passive"))
      (node (ref "SLAVE") (pin "IOREF") (pinfunction "IOREF_IOREF") (pintype "bidirectional"))
    )
    (net (code "184") (name "RST") (class "Default")
      (node (ref "M7") (pin "3") (pinfunction "3_3") (pintype "passive"))
      (node (ref "MASTER") (pin "RST") (pinfunction "RST_RST") (pintype "bidirectional"))
      (node (ref "MASTER") (pin "RST1") (pinfunction "RST1_RST1") (pintype "bidirectional"))
      (node (ref "RESET") (pin "1") (pinfunction "1_1") (pintype "passive"))
      (node (ref "U$4") (pin "RST") (pinfunction "RST_RST") (pintype "bidirectional"))
      (node (ref "U$4") (pin "RST1") (pinfunction "RST1_RST1") (pintype "bidirectional"))
    )
    (net (code "185") (name "S-5V") (class "Default")
      (node (ref "5V") (pin "2") (pinfunction "2_2") (pintype "passive"))
      (node (ref "I2C2P") (pin "1") (pinfunction "1_1") (pintype "passive"))
      (node (ref "IMU_BLOCK3") (pin "4") (pinfunction "4_4") (pintype "bidirectional"))
      (node (ref "S-4") (pin "1") (pinfunction "1_1") (pintype "passive"))
      (node (ref "S-4") (pin "2") (pinfunction "2_2") (pintype "passive"))
      (node (ref "S-ICSP") (pin "1") (pinfunction "1_1") (pintype "passive"))
      (node (ref "S7") (pin "5") (pinfunction "5_5") (pintype "passive"))
      (node (ref "SLAVE") (pin "5V") (pinfunction "5V_5V") (pintype "bidirectional"))
      (node (ref "SLAVE") (pin "5V1") (pinfunction "5V1_5V1") (pintype "bidirectional"))
      (node (ref "SLAVE") (pin "5V2") (pinfunction "5V2_5V2") (pintype "bidirectional"))
      (node (ref "SLAVE") (pin "5V3") (pinfunction "5V3_5V3") (pintype "bidirectional"))
    )
    (net (code "186") (name "S-MISO") (class "Default")
      (node (ref "S-ICSP") (pin "2") (pinfunction "2_2") (pintype "passive"))
      (node (ref "SLAVE") (pin "MISO") (pinfunction "MISO_MISO") (pintype "bidirectional"))
    )
    (net (code "187") (name "S-MOSI") (class "Default")
      (node (ref "S-ICSP") (pin "3") (pinfunction "3_3") (pintype "passive"))
      (node (ref "SLAVE") (pin "MOSI") (pinfunction "MOSI_MOSI") (pintype "bidirectional"))
    )
    (net (code "188") (name "S-RST") (class "Default")
      (node (ref "RESET") (pin "2") (pinfunction "2_2") (pintype "passive"))
      (node (ref "S-ICSP") (pin "6") (pinfunction "6_6") (pintype "passive"))
      (node (ref "S7") (pin "3") (pinfunction "3_3") (pintype "passive"))
      (node (ref "SLAVE") (pin "RST") (pinfunction "RST_RST") (pintype "bidirectional"))
      (node (ref "SLAVE") (pin "RST1") (pinfunction "RST1_RST1") (pintype "bidirectional"))
    )
    (net (code "189") (name "S-SCK") (class "Default")
      (node (ref "S-ICSP") (pin "4") (pinfunction "4_4") (pintype "passive"))
      (node (ref "SLAVE") (pin "SCK") (pinfunction "SCK_SCK") (pintype "bidirectional"))
    )
    (net (code "190") (name "S-SCL") (class "Default")
      (node (ref "I2C2P") (pin "2") (pinfunction "2_2") (pintype "passive"))
      (node (ref "IMU_BLOCK3") (pin "2") (pinfunction "2_2") (pintype "bidirectional"))
      (node (ref "IMU_BLOCK4") (pin "2") (pinfunction "2_2") (pintype "bidirectional"))
      (node (ref "S-3") (pin "1") (pinfunction "1_1") (pintype "passive"))
      (node (ref "S1") (pin "10") (pinfunction "10_10") (pintype "passive"))
      (node (ref "SLAVE") (pin "SCL") (pinfunction "SCL_SCL") (pintype "bidirectional"))
      (node (ref "SLAVE") (pin "SCLU") (pinfunction "SCLU_SCLU") (pintype "bidirectional"))
    )
    (net (code "191") (name "S-SDA") (class "Default")
      (node (ref "I2C2P") (pin "3") (pinfunction "3_3") (pintype "passive"))
      (node (ref "IMU_BLOCK3") (pin "1") (pinfunction "1_1") (pintype "bidirectional"))
      (node (ref "IMU_BLOCK4") (pin "1") (pinfunction "1_1") (pintype "bidirectional"))
      (node (ref "S-3") (pin "2") (pinfunction "2_2") (pintype "passive"))
      (node (ref "S1") (pin "9") (pinfunction "9_9") (pintype "passive"))
      (node (ref "SLAVE") (pin "SDA") (pinfunction "SDA_SDA") (pintype "bidirectional"))
      (node (ref "SLAVE") (pin "SDAU") (pinfunction "SDAU_SDAU") (pintype "bidirectional"))
    )
    (net (code "192") (name "SCK") (class "Default")
      (node (ref "MASTER") (pin "SCK") (pinfunction "SCK_SCK") (pintype "bidirectional"))
      (node (ref "U$4") (pin "SCK") (pinfunction "SC_SCK") (pintype "bidirectional"))
    )
    (net (code "193") (name "SCL") (class "Default")
      (node (ref "I2C1P") (pin "2") (pinfunction "2_2") (pintype "passive"))
      (node (ref "IMU_BLOCK2") (pin "2") (pinfunction "2_2") (pintype "bidirectional"))
      (node (ref "IMU_MASTER") (pin "2") (pinfunction "2_2") (pintype "bidirectional"))
      (node (ref "M1") (pin "10") (pinfunction "10_10") (pintype "passive"))
      (node (ref "M3") (pin "1") (pinfunction "1_1") (pintype "passive"))
      (node (ref "MASTER") (pin "SCL") (pinfunction "SCL_SCL") (pintype "bidirectional"))
      (node (ref "MASTER") (pin "SCLU") (pinfunction "SCLU_SCLU") (pintype "bidirectional"))
      (node (ref "U$4") (pin "SCL") (pinfunction "SCL_SCL") (pintype "bidirectional"))
    )
    (net (code "194") (name "SDA") (class "Default")
      (node (ref "I2C1P") (pin "3") (pinfunction "3_3") (pintype "passive"))
      (node (ref "IMU_BLOCK2") (pin "1") (pinfunction "1_1") (pintype "bidirectional"))
      (node (ref "IMU_MASTER") (pin "1") (pinfunction "1_1") (pintype "bidirectional"))
      (node (ref "M1") (pin "9") (pinfunction "9_9") (pintype "passive"))
      (node (ref "M3") (pin "2") (pinfunction "2_2") (pintype "passive"))
      (node (ref "MASTER") (pin "SDA") (pinfunction "SDA_SDA") (pintype "bidirectional"))
      (node (ref "MASTER") (pin "SDAU") (pinfunction "SDAU_SDAU") (pintype "bidirectional"))
      (node (ref "U$4") (pin "SDA") (pinfunction "SDA_SDA") (pintype "bidirectional"))
    )
    (net (code "195") (name "VCC") (class "Default")
      (node (ref "LM358") (pin "8") (pinfunction "8_8") (pintype "passive"))
      (node (ref "P1") (pin "3") (pinfunction "3_3") (pintype "bidirectional"))
      (node (ref "P2") (pin "3") (pinfunction "3_3") (pintype "bidirectional"))
      (node (ref "P3") (pin "3") (pinfunction "3_3") (pintype "bidirectional"))
      (node (ref "P4") (pin "3") (pinfunction "3_3") (pintype "bidirectional"))
      (node (ref "SUPPLY") (pin "1") (pinfunction "1_1") (pintype "bidirectional"))
      (node (ref "U$3") (pin "IN+") (pinfunction "IN+_IN+") (pintype "bidirectional"))
      (node (ref "ULN") (pin "9") (pinfunction "9_9") (pintype "passive"))
      (node (ref "ULN_SUPPLY") (pin "1") (pinfunction "1_1") (pintype "bidirectional"))
      (node (ref "ULN_SUPPLY") (pin "2") (pinfunction "2_2") (pintype "bidirectional"))
      (node (ref "ULN_SUPPLY1") (pin "1") (pinfunction "1_1") (pintype "bidirectional"))
      (node (ref "ULN_SUPPLY1") (pin "2") (pinfunction "2_2") (pintype "bidirectional"))
      (node (ref "VCC-GND") (pin "1") (pinfunction "1_1") (pintype "bidirectional"))
    )
    (net (code "196") (name "unconnected-(I2C1P-Pad4)") (class "Default")
      (node (ref "I2C1P") (pin "4") (pinfunction "4_4") (pintype "passive"))
    )
    (net (code "197") (name "unconnected-(I2C2P-Pad4)") (class "Default")
      (node (ref "I2C2P") (pin "4") (pinfunction "4_4") (pintype "passive"))
    )
    (net (code "198") (name "unconnected-(U$1-Pad1)") (class "Default")
      (node (ref "U$1") (pin "1") (pinfunction "1_1") (pintype "bidirectional"))
    )
    (net (code "199") (name "unconnected-(U$2-Pad1)") (class "Default")
      (node (ref "U$2") (pin "1") (pinfunction "1_1") (pintype "bidirectional"))
    )
    (net (code "200") (name "unconnected-(U$4-Pad-)") (class "Default")
      (node (ref "U$4") (pin "-") (pinfunction "-_-") (pintype "bidirectional"))
    )
    (net (code "201") (name "unconnected-(U$5-Pad1)") (class "Default")
      (node (ref "U$5") (pin "1") (pinfunction "1_1") (pintype "bidirectional"))
    )
    (net (code "202") (name "unconnected-(U$6-Pad1)") (class "Default")
      (node (ref "U$6") (pin "1") (pinfunction "1_1") (pintype "bidirectional"))
    )
    (net (code "203") (name "unconnected-(U$7-Pad1)") (class "Default")
      (node (ref "U$7") (pin "1") (pinfunction "1_1") (pintype "bidirectional"))
    )
    (net (code "204") (name "unconnected-(U$8-Pad1)") (class "Default")
      (node (ref "U$8") (pin "1") (pinfunction "1_1") (pintype "bidirectional"))
    )
    (net (code "205") (name "unconnected-(ULN-Pad6)") (class "Default")
      (node (ref "ULN") (pin "6") (pinfunction "6_6") (pintype "passive"))
    )
    (net (code "206") (name "unconnected-(ULN-Pad7)") (class "Default")
      (node (ref "ULN") (pin "7") (pinfunction "7_7") (pintype "passive"))
    )
    (net (code "207") (name "unconnected-(ULN-Pad10)") (class "Default")
      (node (ref "ULN") (pin "10") (pinfunction "10_10") (pintype "passive"))
    )
    (net (code "208") (name "unconnected-(ULN-Pad11)") (class "Default")
      (node (ref "ULN") (pin "11") (pinfunction "11_11") (pintype "passive"))
    )
  )
)
